# lamloei_unofox_sfm10r4.net
KiCad netlist of a schematic drawn in EAGLE
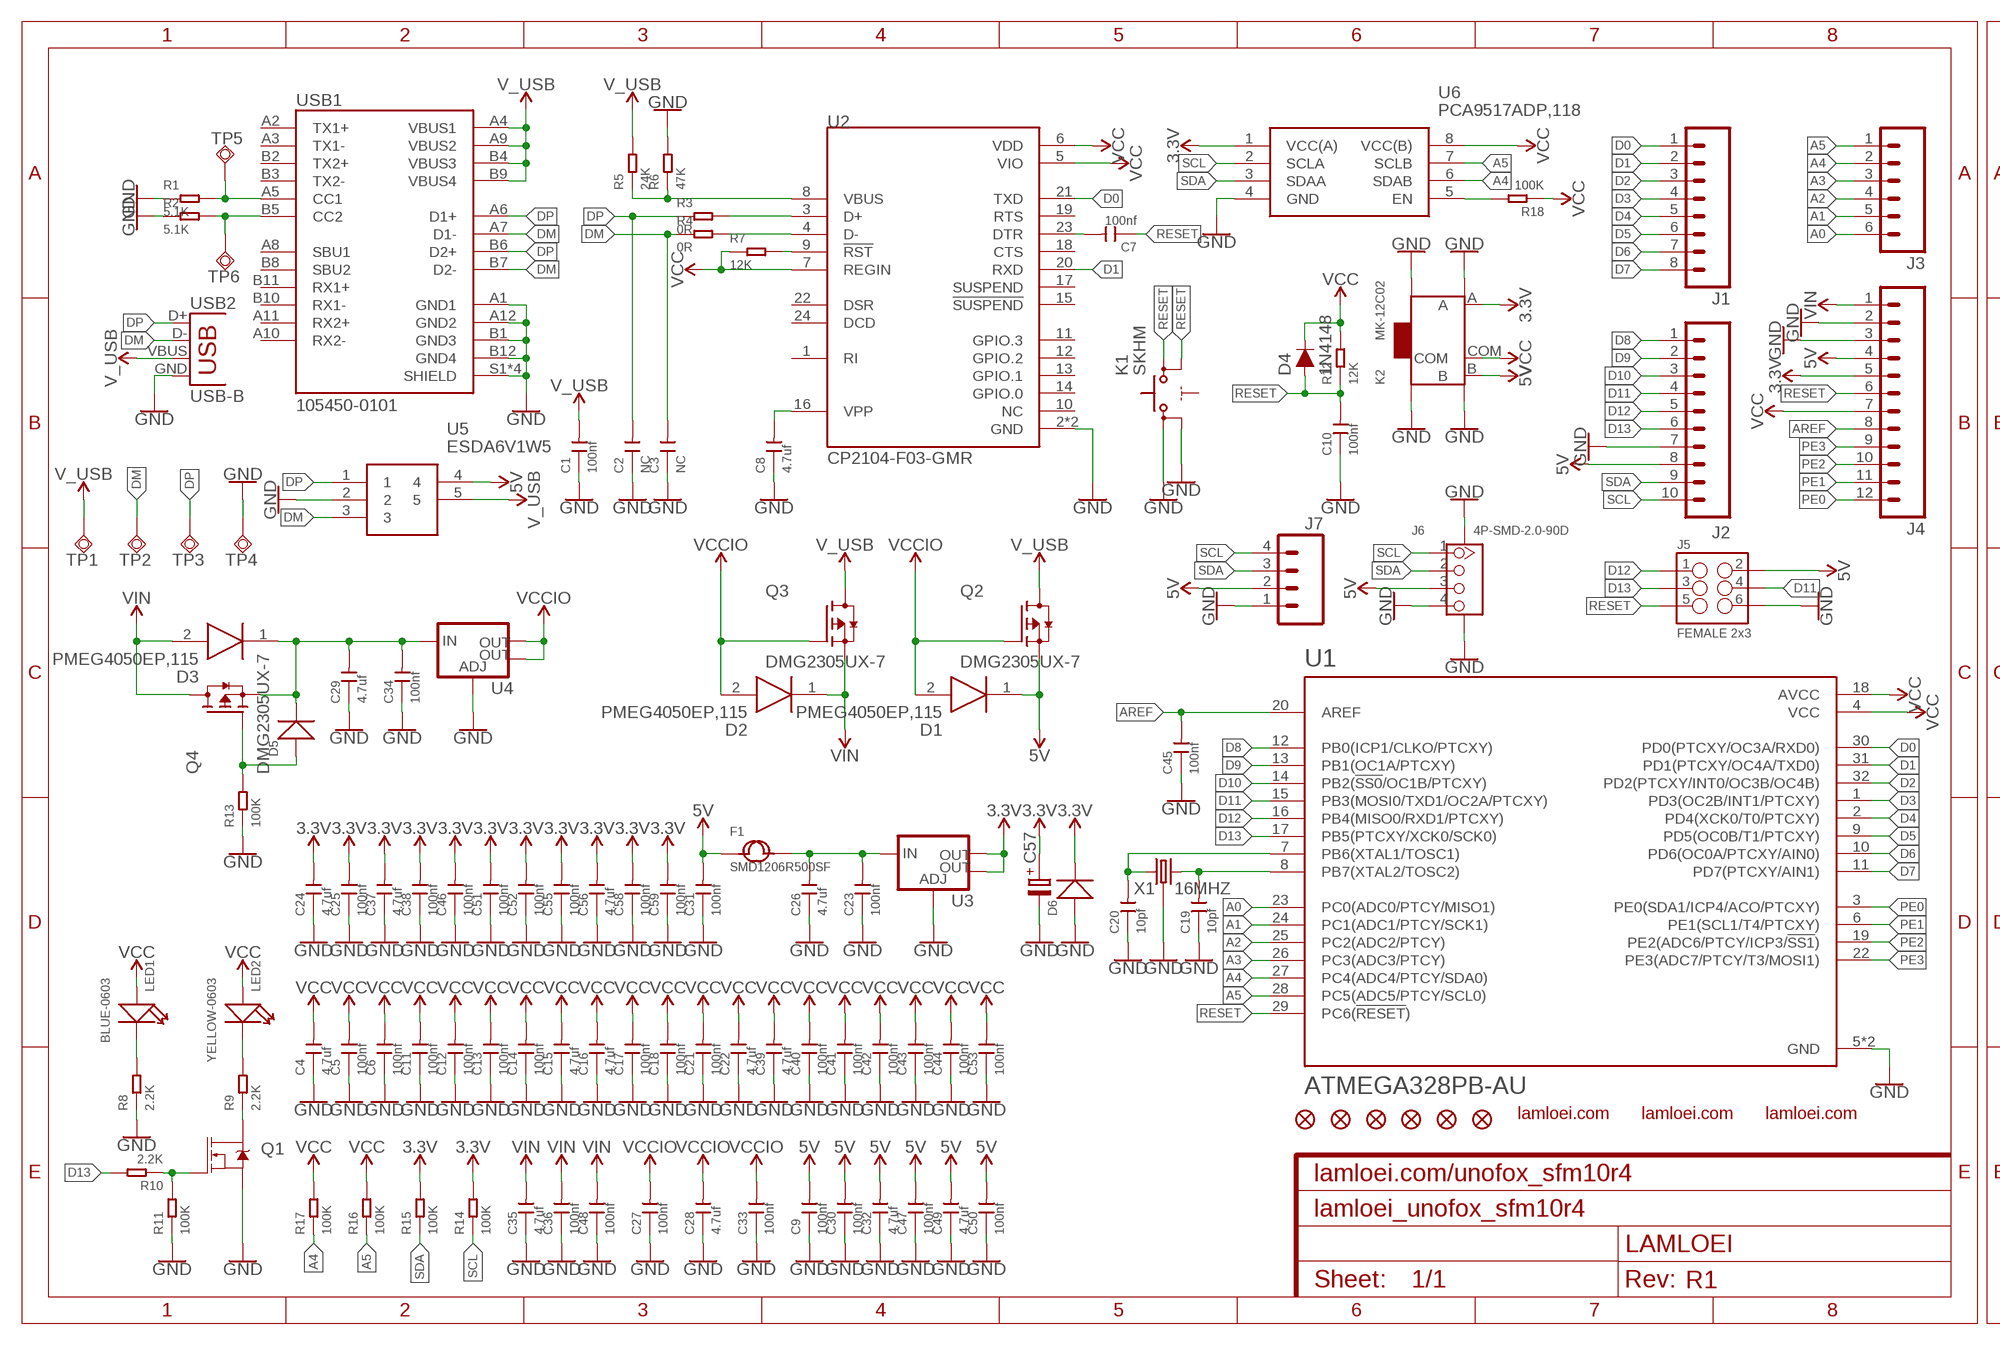
[diagram p0: schematic, sheet 1, part 1 of 2]
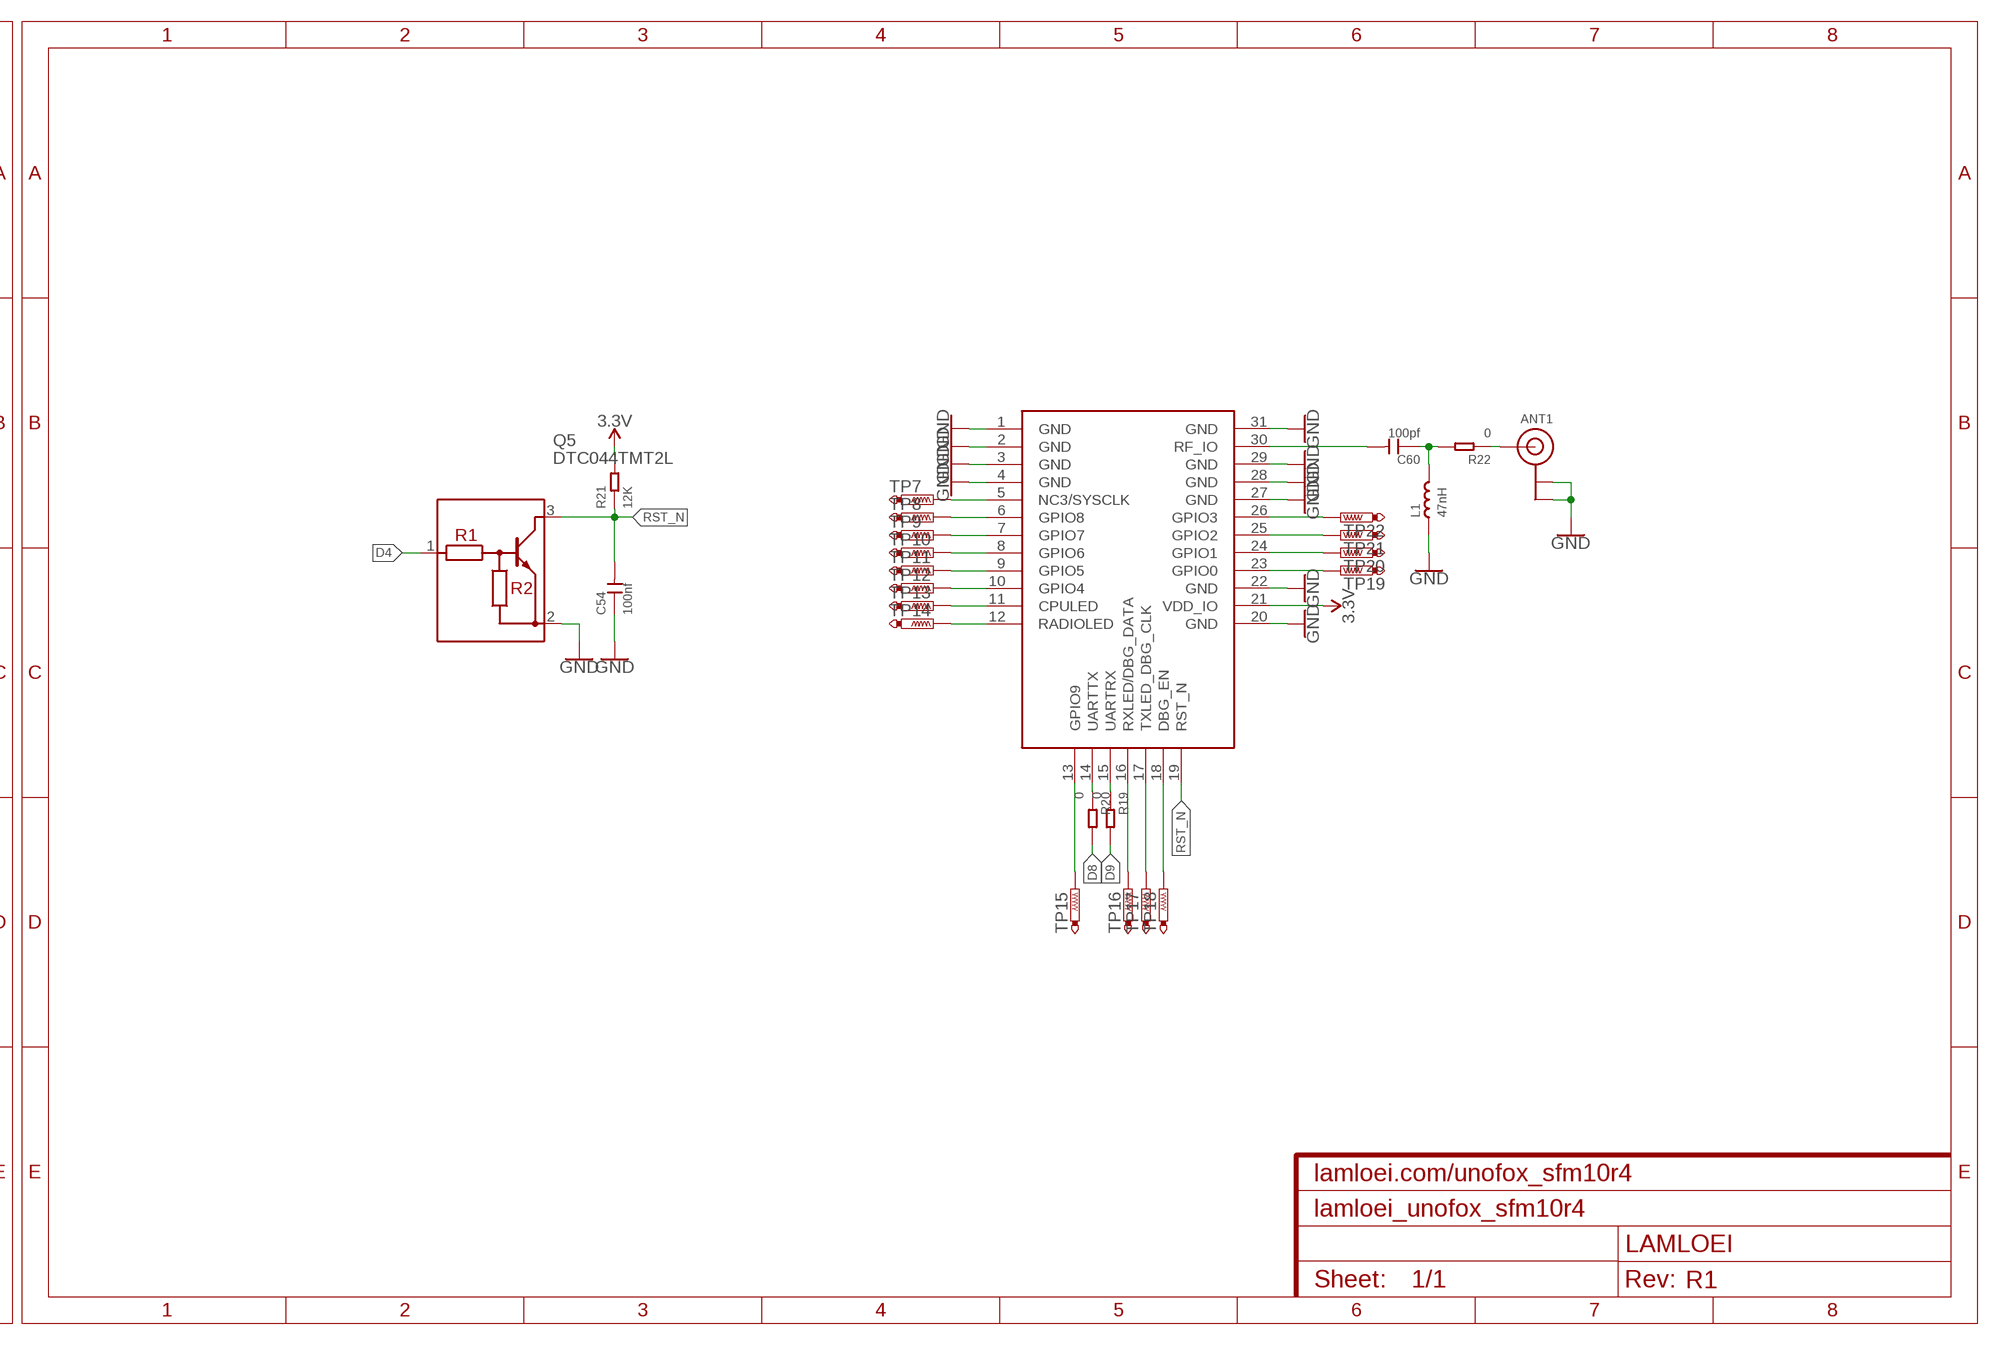
[diagram p1: schematic, sheet 1, part 2 of 2]

(export (version "E")
  (design (tool "Eeschema 10.0.6"))
  (components
    (comp (ref "ANT1")
      (value "ANTENNA_U.FL")
      (footprint "eagle-import:U.FL")
      (libsource (lib "eagle-import") (part "ANTENNA_U.FL"))
    )
    (comp (ref "C1")
      (value "100nf")
      (footprint "eagle-import:C0402")
      (fields (field (name "MPN") "CC0402KRX7R8BB104"))
      (libsource (lib "eagle-import") (part "CERAMIC-100NF-25V-10%-X7R(0402)"))
    )
    (comp (ref "C2")
      (value "NC")
      (footprint "eagle-import:C0402")
      (fields (field (name "MPN") "CC0402JRNPO9BN470"))
      (libsource (lib "eagle-import") (part "CERAMIC-47PF-50V-5%-NP0(0402)"))
    )
    (comp (ref "C3")
      (value "NC")
      (footprint "eagle-import:C0402")
      (fields (field (name "MPN") "CC0402JRNPO9BN470"))
      (libsource (lib "eagle-import") (part "CERAMIC-47PF-50V-5%-NP0(0402)"))
    )
    (comp (ref "C4")
      (value "4.7uf")
      (footprint "eagle-import:C0805")
      (fields (field (name "MPN") "CC0805KKX5R8BB106"))
      (libsource (lib "eagle-import") (part "CERAMIC-10UF-25V-10%-X5R(0805)"))
    )
    (comp (ref "C5")
      (value "100nf")
      (footprint "eagle-import:C0402")
      (fields (field (name "MPN") "CC0402KRX7R8BB104"))
      (libsource (lib "eagle-import") (part "CERAMIC-100NF-25V-10%-X7R(0402)"))
    )
    (comp (ref "C6")
      (value "100nf")
      (footprint "eagle-import:C0402")
      (fields (field (name "MPN") "CC0402KRX7R8BB104"))
      (libsource (lib "eagle-import") (part "CERAMIC-100NF-25V-10%-X7R(0402)"))
    )
    (comp (ref "C7")
      (value "100nf")
      (footprint "eagle-import:C0402")
      (fields (field (name "MPN") "CC0402KRX7R8BB104"))
      (libsource (lib "eagle-import") (part "CERAMIC-100NF-25V-10%-X7R(0402)"))
    )
    (comp (ref "C8")
      (value "4.7uf")
      (footprint "eagle-import:C0805")
      (fields (field (name "MPN") "CC0805KKX5R8BB106"))
      (libsource (lib "eagle-import") (part "CERAMIC-10UF-25V-10%-X5R(0805)"))
    )
    (comp (ref "C9")
      (value "100nf")
      (footprint "eagle-import:C0402")
      (fields (field (name "MPN") "CC0402KRX7R8BB104"))
      (libsource (lib "eagle-import") (part "CERAMIC-100NF-25V-10%-X7R(0402)"))
    )
    (comp (ref "C10")
      (value "100nf")
      (footprint "eagle-import:C0402")
      (fields (field (name "MPN") "CC0402KRX7R8BB104"))
      (libsource (lib "eagle-import") (part "CERAMIC-100NF-25V-10%-X7R(0402)"))
    )
    (comp (ref "C11")
      (value "100nf")
      (footprint "eagle-import:C0402")
      (fields (field (name "MPN") "CC0402KRX7R8BB104"))
      (libsource (lib "eagle-import") (part "CERAMIC-100NF-25V-10%-X7R(0402)"))
    )
    (comp (ref "C12")
      (value "100nf")
      (footprint "eagle-import:C0402")
      (fields (field (name "MPN") "CC0402KRX7R8BB104"))
      (libsource (lib "eagle-import") (part "CERAMIC-100NF-25V-10%-X7R(0402)"))
    )
    (comp (ref "C13")
      (value "100nf")
      (footprint "eagle-import:C0402")
      (fields (field (name "MPN") "CC0402KRX7R8BB104"))
      (libsource (lib "eagle-import") (part "CERAMIC-100NF-25V-10%-X7R(0402)"))
    )
    (comp (ref "C14")
      (value "100nf")
      (footprint "eagle-import:C0402")
      (fields (field (name "MPN") "CC0402KRX7R8BB104"))
      (libsource (lib "eagle-import") (part "CERAMIC-100NF-25V-10%-X7R(0402)"))
    )
    (comp (ref "C15")
      (value "4.7uf")
      (footprint "eagle-import:C0805")
      (fields (field (name "MPN") "CC0805KKX5R8BB106"))
      (libsource (lib "eagle-import") (part "CERAMIC-10UF-25V-10%-X5R(0805)"))
    )
    (comp (ref "C16")
      (value "4.7uf")
      (footprint "eagle-import:C0805")
      (fields (field (name "MPN") "CC0805KKX5R8BB106"))
      (libsource (lib "eagle-import") (part "CERAMIC-10UF-25V-10%-X5R(0805)"))
    )
    (comp (ref "C17")
      (value "100nf")
      (footprint "eagle-import:C0402")
      (fields (field (name "MPN") "CC0402KRX7R8BB104"))
      (libsource (lib "eagle-import") (part "CERAMIC-100NF-25V-10%-X7R(0402)"))
    )
    (comp (ref "C18")
      (value "100nf")
      (footprint "eagle-import:C0402")
      (fields (field (name "MPN") "CC0402KRX7R8BB104"))
      (libsource (lib "eagle-import") (part "CERAMIC-100NF-25V-10%-X7R(0402)"))
    )
    (comp (ref "C19")
      (value "10pf")
      (footprint "eagle-import:C0402")
      (fields (field (name "MPN") "CC0402KRX7R8BB104"))
      (libsource (lib "eagle-import") (part "CERAMIC-100NF-25V-10%-X7R(0402)"))
    )
    (comp (ref "C20")
      (value "10pf")
      (footprint "eagle-import:C0402")
      (fields (field (name "MPN") "CC0402KRX7R8BB104"))
      (libsource (lib "eagle-import") (part "CERAMIC-100NF-25V-10%-X7R(0402)"))
    )
    (comp (ref "C21")
      (value "100nf")
      (footprint "eagle-import:C0402")
      (fields (field (name "MPN") "CC0402KRX7R8BB104"))
      (libsource (lib "eagle-import") (part "CERAMIC-100NF-25V-10%-X7R(0402)"))
    )
    (comp (ref "C22")
      (value "4.7uf")
      (footprint "eagle-import:C0805")
      (fields (field (name "MPN") "CC0805KKX5R8BB106"))
      (libsource (lib "eagle-import") (part "CERAMIC-10UF-25V-10%-X5R(0805)"))
    )
    (comp (ref "C23")
      (value "100nf")
      (footprint "eagle-import:C0402")
      (fields (field (name "MPN") "CC0402KRX7R8BB104"))
      (libsource (lib "eagle-import") (part "CERAMIC-100NF-25V-10%-X7R(0402)"))
    )
    (comp (ref "C24")
      (value "4.7uf")
      (footprint "eagle-import:C0805")
      (fields (field (name "MPN") "CC0805KKX5R8BB106"))
      (libsource (lib "eagle-import") (part "CERAMIC-10UF-25V-10%-X5R(0805)"))
    )
    (comp (ref "C25")
      (value "100nf")
      (footprint "eagle-import:C0402")
      (fields (field (name "MPN") "CC0402KRX7R8BB104"))
      (libsource (lib "eagle-import") (part "CERAMIC-100NF-25V-10%-X7R(0402)"))
    )
    (comp (ref "C26")
      (value "4.7uf")
      (footprint "eagle-import:C0805")
      (fields (field (name "MPN") "CC0805KKX5R8BB106"))
      (libsource (lib "eagle-import") (part "CERAMIC-10UF-25V-10%-X5R(0805)"))
    )
    (comp (ref "C27")
      (value "100nf")
      (footprint "eagle-import:C0402")
      (fields (field (name "MPN") "CC0402KRX7R8BB104"))
      (libsource (lib "eagle-import") (part "CERAMIC-100NF-25V-10%-X7R(0402)"))
    )
    (comp (ref "C28")
      (value "4.7uf")
      (footprint "eagle-import:C0805")
      (fields (field (name "MPN") "CC0805KKX5R8BB106"))
      (libsource (lib "eagle-import") (part "CERAMIC-10UF-25V-10%-X5R(0805)"))
    )
    (comp (ref "C29")
      (value "4.7uf")
      (footprint "eagle-import:C0805")
      (fields (field (name "MPN") "CC0805KKX5R8BB106"))
      (libsource (lib "eagle-import") (part "CERAMIC-10UF-25V-10%-X5R(0805)"))
    )
    (comp (ref "C30")
      (value "100nf")
      (footprint "eagle-import:C0402")
      (fields (field (name "MPN") "CC0402KRX7R8BB104"))
      (libsource (lib "eagle-import") (part "CERAMIC-100NF-25V-10%-X7R(0402)"))
    )
    (comp (ref "C31")
      (value "100nf")
      (footprint "eagle-import:C0402")
      (fields (field (name "MPN") "CC0402KRX7R8BB104"))
      (libsource (lib "eagle-import") (part "CERAMIC-100NF-25V-10%-X7R(0402)"))
    )
    (comp (ref "C32")
      (value "4.7uf")
      (footprint "eagle-import:C0805")
      (fields (field (name "MPN") "CC0805KKX5R8BB106"))
      (libsource (lib "eagle-import") (part "CERAMIC-10UF-25V-10%-X5R(0805)"))
    )
    (comp (ref "C33")
      (value "100nf")
      (footprint "eagle-import:C0402")
      (fields (field (name "MPN") "CC0402KRX7R8BB104"))
      (libsource (lib "eagle-import") (part "CERAMIC-100NF-25V-10%-X7R(0402)"))
    )
    (comp (ref "C34")
      (value "100nf")
      (footprint "eagle-import:C0402")
      (fields (field (name "MPN") "CC0402KRX7R8BB104"))
      (libsource (lib "eagle-import") (part "CERAMIC-100NF-25V-10%-X7R(0402)"))
    )
    (comp (ref "C35")
      (value "4.7uf")
      (footprint "eagle-import:C0805")
      (fields (field (name "MPN") "CC0805KKX5R8BB106"))
      (libsource (lib "eagle-import") (part "CERAMIC-10UF-25V-10%-X5R(0805)"))
    )
    (comp (ref "C36")
      (value "100nf")
      (footprint "eagle-import:C0402")
      (fields (field (name "MPN") "CC0402KRX7R8BB104"))
      (libsource (lib "eagle-import") (part "CERAMIC-100NF-25V-10%-X7R(0402)"))
    )
    (comp (ref "C37")
      (value "4.7uf")
      (footprint "eagle-import:C0805")
      (fields (field (name "MPN") "CC0805KKX5R8BB106"))
      (libsource (lib "eagle-import") (part "CERAMIC-10UF-25V-10%-X5R(0805)"))
    )
    (comp (ref "C38")
      (value "100nf")
      (footprint "eagle-import:C0402")
      (fields (field (name "MPN") "CC0402KRX7R8BB104"))
      (libsource (lib "eagle-import") (part "CERAMIC-100NF-25V-10%-X7R(0402)"))
    )
    (comp (ref "C39")
      (value "4.7uf")
      (footprint "eagle-import:C0805")
      (fields (field (name "MPN") "CC0805KKX5R8BB106"))
      (libsource (lib "eagle-import") (part "CERAMIC-10UF-25V-10%-X5R(0805)"))
    )
    (comp (ref "C40")
      (value "100nf")
      (footprint "eagle-import:C0402")
      (fields (field (name "MPN") "CC0402KRX7R8BB104"))
      (libsource (lib "eagle-import") (part "CERAMIC-100NF-25V-10%-X7R(0402)"))
    )
    (comp (ref "C41")
      (value "100nf")
      (footprint "eagle-import:C0402")
      (fields (field (name "MPN") "CC0402KRX7R8BB104"))
      (libsource (lib "eagle-import") (part "CERAMIC-100NF-25V-10%-X7R(0402)"))
    )
    (comp (ref "C42")
      (value "100nf")
      (footprint "eagle-import:C0402")
      (fields (field (name "MPN") "CC0402KRX7R8BB104"))
      (libsource (lib "eagle-import") (part "CERAMIC-100NF-25V-10%-X7R(0402)"))
    )
    (comp (ref "C43")
      (value "100nf")
      (footprint "eagle-import:C0402")
      (fields (field (name "MPN") "CC0402KRX7R8BB104"))
      (libsource (lib "eagle-import") (part "CERAMIC-100NF-25V-10%-X7R(0402)"))
    )
    (comp (ref "C44")
      (value "100nf")
      (footprint "eagle-import:C0402")
      (fields (field (name "MPN") "CC0402KRX7R8BB104"))
      (libsource (lib "eagle-import") (part "CERAMIC-100NF-25V-10%-X7R(0402)"))
    )
    (comp (ref "C45")
      (value "100nf")
      (footprint "eagle-import:C0402")
      (fields (field (name "MPN") "CC0402KRX7R8BB104"))
      (libsource (lib "eagle-import") (part "CERAMIC-100NF-25V-10%-X7R(0402)"))
    )
    (comp (ref "C46")
      (value "100nf")
      (footprint "eagle-import:C0402")
      (fields (field (name "MPN") "CC0402KRX7R8BB104"))
      (libsource (lib "eagle-import") (part "CERAMIC-100NF-25V-10%-X7R(0402)"))
    )
    (comp (ref "C47")
      (value "100nf")
      (footprint "eagle-import:C0402")
      (fields (field (name "MPN") "CC0402KRX7R8BB104"))
      (libsource (lib "eagle-import") (part "CERAMIC-100NF-25V-10%-X7R(0402)"))
    )
    (comp (ref "C48")
      (value "100nf")
      (footprint "eagle-import:C0402")
      (fields (field (name "MPN") "CC0402KRX7R8BB104"))
      (libsource (lib "eagle-import") (part "CERAMIC-100NF-25V-10%-X7R(0402)"))
    )
    (comp (ref "C49")
      (value "4.7uf")
      (footprint "eagle-import:C0805")
      (fields (field (name "MPN") "CC0805KKX5R8BB106"))
      (libsource (lib "eagle-import") (part "CERAMIC-10UF-25V-10%-X5R(0805)"))
    )
    (comp (ref "C50")
      (value "100nf")
      (footprint "eagle-import:C0402")
      (fields (field (name "MPN") "CC0402KRX7R8BB104"))
      (libsource (lib "eagle-import") (part "CERAMIC-100NF-25V-10%-X7R(0402)"))
    )
    (comp (ref "C51")
      (value "100nf")
      (footprint "eagle-import:C0402")
      (fields (field (name "MPN") "CC0402KRX7R8BB104"))
      (libsource (lib "eagle-import") (part "CERAMIC-100NF-25V-10%-X7R(0402)"))
    )
    (comp (ref "C52")
      (value "100nf")
      (footprint "eagle-import:C0402")
      (fields (field (name "MPN") "CC0402KRX7R8BB104"))
      (libsource (lib "eagle-import") (part "CERAMIC-100NF-25V-10%-X7R(0402)"))
    )
    (comp (ref "C53")
      (value "100nf")
      (footprint "eagle-import:C0402")
      (fields (field (name "MPN") "CC0402KRX7R8BB104"))
      (libsource (lib "eagle-import") (part "CERAMIC-100NF-25V-10%-X7R(0402)"))
    )
    (comp (ref "C54")
      (value "100nf")
      (footprint "eagle-import:C0402")
      (fields (field (name "MPN") "CC0402KRX7R8BB104"))
      (libsource (lib "eagle-import") (part "CERAMIC-100NF-25V-10%-X7R(0402)"))
    )
    (comp (ref "C55")
      (value "100nf")
      (footprint "eagle-import:C0402")
      (fields (field (name "MPN") "CC0402KRX7R8BB104"))
      (libsource (lib "eagle-import") (part "CERAMIC-100NF-25V-10%-X7R(0402)"))
    )
    (comp (ref "C56")
      (value "4.7uf")
      (footprint "eagle-import:C0805")
      (fields (field (name "MPN") "CC0805KKX5R8BB106"))
      (libsource (lib "eagle-import") (part "CERAMIC-10UF-25V-10%-X5R(0805)"))
    )
    (comp (ref "C57")
      (value "C-PR-SMD-TE-D")
      (footprint "eagle-import:TE-D-7343")
      (libsource (lib "eagle-import") (part "C-PR-SMD-TE-D"))
    )
    (comp (ref "C58")
      (value "100nf")
      (footprint "eagle-import:C0402")
      (fields (field (name "MPN") "CC0402KRX7R8BB104"))
      (libsource (lib "eagle-import") (part "CERAMIC-100NF-25V-10%-X7R(0402)"))
    )
    (comp (ref "C59")
      (value "100nf")
      (footprint "eagle-import:C0402")
      (fields (field (name "MPN") "CC0402KRX7R8BB104"))
      (libsource (lib "eagle-import") (part "CERAMIC-100NF-25V-10%-X7R(0402)"))
    )
    (comp (ref "C60")
      (value "100pf")
      (footprint "eagle-import:C0402")
      (fields (field (name "MPN") "CC0402KRX7R8BB104"))
      (libsource (lib "eagle-import") (part "CERAMIC-100NF-25V-10%-X7R(0402)"))
    )
    (comp (ref "D1")
      (value "PMEG4050EP,115")
      (footprint "eagle-import:SODFL4725X110N")
      (fields (field (name "RS_PART_NUMBER") "7805405P"))
      (libsource (lib "eagle-import") (part "PMEG4050EP,115"))
    )
    (comp (ref "D2")
      (value "PMEG4050EP,115")
      (footprint "eagle-import:SODFL4725X110N")
      (fields (field (name "RS_PART_NUMBER") "7805405P"))
      (libsource (lib "eagle-import") (part "PMEG4050EP,115"))
    )
    (comp (ref "D3")
      (value "PMEG4050EP,115")
      (footprint "eagle-import:SODFL4725X110N")
      (fields (field (name "RS_PART_NUMBER") "7805405P"))
      (libsource (lib "eagle-import") (part "PMEG4050EP,115"))
    )
    (comp (ref "D4")
      (value "1N4148")
      (footprint "eagle-import:SOD-323")
      (libsource (lib "eagle-import") (part "DIODE-BAS16J"))
    )
    (comp (ref "D5")
      (value "DIODE'1N4148-SMD'")
      (footprint "eagle-import:LL-34")
      (libsource (lib "eagle-import") (part "DIODE'1N4148-SMD'"))
    )
    (comp (ref "D6")
      (value "DIODE'1N4148-SMD'")
      (footprint "eagle-import:LL-34")
      (libsource (lib "eagle-import") (part "DIODE'1N4148-SMD'"))
    )
    (comp (ref "F1")
      (value "SMD1206R500SF")
      (footprint "eagle-import:F1206")
      (libsource (lib "eagle-import") (part "SMD-PPTC-500MA(1206)"))
    )
    (comp (ref "J1")
      (value "M08SILK_FEMALE_PTH")
      (footprint "eagle-import:1X08")
      (libsource (lib "eagle-import") (part "M08SILK_FEMALE_PTH"))
    )
    (comp (ref "J2")
      (value "M10SILK_FEMALE_PTH")
      (footprint "eagle-import:1X10")
      (libsource (lib "eagle-import") (part "M10SILK_FEMALE_PTH"))
    )
    (comp (ref "J3")
      (value "M06SILK_FEMALE_PTH")
      (footprint "eagle-import:1X06")
      (libsource (lib "eagle-import") (part "M06SILK_FEMALE_PTH"))
    )
    (comp (ref "J4")
      (value "M12PTH")
      (footprint "eagle-import:1X12")
      (libsource (lib "eagle-import") (part "M12PTH"))
    )
    (comp (ref "J5")
      (value "FEMALE 2x3")
      (footprint "eagle-import:2X3")
      (libsource (lib "eagle-import") (part "M03X2FEMALE"))
    )
    (comp (ref "J6")
      (value "4P-SMD-2.0-90D")
      (footprint "eagle-import:HW4-SMD-2.0-90D")
      (libsource (lib "eagle-import") (part "GROVE-CONNECTOR-SMD-90D(4+2P-2.0)"))
    )
    (comp (ref "J7")
      (value "M04LONGPADS")
      (footprint "eagle-import:1X04_LONGPADS")
      (libsource (lib "eagle-import") (part "M04LONGPADS"))
    )
    (comp (ref "K1")
      (value "SKHM")
      (footprint "eagle-import:SKHM")
      (libsource (lib "eagle-import") (part "SKHM"))
    )
    (comp (ref "K2")
      (value "MK-12C02")
      (footprint "eagle-import:SW7-SMD-L6.7X2.7X3.2MM")
      (libsource (lib "eagle-import") (part "SMD-TOGGLE-SWITCH-ON-ON(3+4P-6.7X2.7MM)"))
    )
    (comp (ref "L1")
      (value "47nH")
      (footprint "eagle-import:L0603")
      (libsource (lib "eagle-import") (part "SMD-INDUCTOR-68NH-10%(0603)"))
    )
    (comp (ref "LED1")
      (value "BLUE-0603")
      (footprint "eagle-import:LED-0603")
      (fields (field (name "MPN") "19-217-BHC-ZL1M2RY-3T"))
      (libsource (lib "eagle-import") (part "SMD-LED-CLEAR-BLUE(0603)"))
    )
    (comp (ref "LED2")
      (value "YELLOW-0603")
      (footprint "eagle-import:LED-0603")
      (fields (field (name "MPN") "19-217-BHC-ZL1M2RY-3T"))
      (libsource (lib "eagle-import") (part "SMD-LED-CLEAR-BLUE(0603)"))
    )
    (comp (ref "Q1")
      (value "220mA/50V/3.5Ω")
      (footprint "eagle-import:SOT23-3")
      (libsource (lib "eagle-import") (part "MOSFET-NCH-BSS138"))
    )
    (comp (ref "Q2")
      (value "DMG2305UX-7")
      (footprint "eagle-import:SOT91P240X110-3N_DMG2305UX-7")
      (fields (field (name "MF") "Diodes Inc."))
      (libsource (lib "eagle-import") (part "DMG2305UX-7"))
    )
    (comp (ref "Q3")
      (value "DMG2305UX-7")
      (footprint "eagle-import:SOT91P240X110-3N_DMG2305UX-7")
      (fields (field (name "MF") "Diodes Inc."))
      (libsource (lib "eagle-import") (part "DMG2305UX-7"))
    )
    (comp (ref "Q4")
      (value "DMG2305UX-7")
      (footprint "eagle-import:SOT91P240X110-3N_DMG2305UX-7")
      (fields (field (name "MF") "Diodes Inc."))
      (libsource (lib "eagle-import") (part "DMG2305UX-7"))
    )
    (comp (ref "Q5")
      (value "DTC044TMT2L")
      (footprint "eagle-import:SOTFL40P120X55-3N")
      (fields (field (name "RS_PART_NUMBER") "1467267"))
      (libsource (lib "eagle-import") (part "DTC044TMT2L"))
    )
    (comp (ref "R1")
      (value "5.1K")
      (footprint "eagle-import:R0402")
      (fields (field (name "MPN") "RC0402JR-074K7L"))
      (libsource (lib "eagle-import") (part "SMD-RES-4.7K-5%-1/16W(0402)"))
    )
    (comp (ref "R2")
      (value "5.1K")
      (footprint "eagle-import:R0402")
      (fields (field (name "MPN") "RC0402JR-074K7L"))
      (libsource (lib "eagle-import") (part "SMD-RES-4.7K-5%-1/16W(0402)"))
    )
    (comp (ref "R3")
      (value "0R")
      (footprint "eagle-import:R0402")
      (fields (field (name "MPN") "RC0402FR-0722RL"))
      (libsource (lib "eagle-import") (part "SMD-RES-22R-1%-1/16W(0402)"))
    )
    (comp (ref "R4")
      (value "0R")
      (footprint "eagle-import:R0402")
      (fields (field (name "MPN") "RC0402FR-0722RL"))
      (libsource (lib "eagle-import") (part "SMD-RES-22R-1%-1/16W(0402)"))
    )
    (comp (ref "R5")
      (value "24K")
      (footprint "eagle-import:R0402")
      (fields (field (name "MPN") "RC0402FR-0722RL"))
      (libsource (lib "eagle-import") (part "SMD-RES-22R-1%-1/16W(0402)"))
    )
    (comp (ref "R6")
      (value "47K")
      (footprint "eagle-import:R0402")
      (fields (field (name "MPN") "RC0402FR-0722RL"))
      (libsource (lib "eagle-import") (part "SMD-RES-22R-1%-1/16W(0402)"))
    )
    (comp (ref "R7")
      (value "12K")
      (footprint "eagle-import:R0402")
      (fields (field (name "MPN") "RC0402FR-0710KL"))
      (libsource (lib "eagle-import") (part "SMD-RES-10K-1%-1/16W(0402)"))
    )
    (comp (ref "R8")
      (value "2.2K")
      (footprint "eagle-import:R0402")
      (fields (field (name "MPN") "RC0402FR-072K7L"))
      (libsource (lib "eagle-import") (part "SMD-RES-2.7K-1%-1/16W(0402)"))
    )
    (comp (ref "R9")
      (value "2.2K")
      (footprint "eagle-import:R0402")
      (fields (field (name "MPN") "RC0402FR-072K7L"))
      (libsource (lib "eagle-import") (part "SMD-RES-2.7K-1%-1/16W(0402)"))
    )
    (comp (ref "R10")
      (value "2.2K")
      (footprint "eagle-import:R0402")
      (fields (field (name "MPN") "RC0402FR-072K7L"))
      (libsource (lib "eagle-import") (part "SMD-RES-2.7K-1%-1/16W(0402)"))
    )
    (comp (ref "R11")
      (value "100K")
      (footprint "eagle-import:R0402")
      (fields (field (name "MPN") "RC0402FR-0710KL"))
      (libsource (lib "eagle-import") (part "SMD-RES-10K-1%-1/16W(0402)"))
    )
    (comp (ref "R12")
      (value "12K")
      (footprint "eagle-import:R0402")
      (fields (field (name "MPN") "RC0402FR-0710KL"))
      (libsource (lib "eagle-import") (part "SMD-RES-10K-1%-1/16W(0402)"))
    )
    (comp (ref "R13")
      (value "100K")
      (footprint "eagle-import:R0402")
      (fields (field (name "MPN") "RC0402FR-0710KL"))
      (libsource (lib "eagle-import") (part "SMD-RES-10K-1%-1/16W(0402)"))
    )
    (comp (ref "R14")
      (value "100K")
      (footprint "eagle-import:R0402")
      (fields (field (name "MPN") "RC0402FR-0710KL"))
      (libsource (lib "eagle-import") (part "SMD-RES-10K-1%-1/16W(0402)"))
    )
    (comp (ref "R15")
      (value "100K")
      (footprint "eagle-import:R0402")
      (fields (field (name "MPN") "RC0402FR-0710KL"))
      (libsource (lib "eagle-import") (part "SMD-RES-10K-1%-1/16W(0402)"))
    )
    (comp (ref "R16")
      (value "100K")
      (footprint "eagle-import:R0402")
      (fields (field (name "MPN") "RC0402FR-0710KL"))
      (libsource (lib "eagle-import") (part "SMD-RES-10K-1%-1/16W(0402)"))
    )
    (comp (ref "R17")
      (value "100K")
      (footprint "eagle-import:R0402")
      (fields (field (name "MPN") "RC0402FR-0710KL"))
      (libsource (lib "eagle-import") (part "SMD-RES-10K-1%-1/16W(0402)"))
    )
    (comp (ref "R18")
      (value "100K")
      (footprint "eagle-import:R0402")
      (fields (field (name "MPN") "RC0402FR-0710KL"))
      (libsource (lib "eagle-import") (part "SMD-RES-10K-1%-1/16W(0402)"))
    )
    (comp (ref "R19")
      (value "0")
      (footprint "eagle-import:R0402")
      (fields (field (name "MPN") "RC0402FR-0710KL"))
      (libsource (lib "eagle-import") (part "SMD-RES-10K-1%-1/16W(0402)"))
    )
    (comp (ref "R20")
      (value "0")
      (footprint "eagle-import:R0402")
      (fields (field (name "MPN") "RC0402FR-0710KL"))
      (libsource (lib "eagle-import") (part "SMD-RES-10K-1%-1/16W(0402)"))
    )
    (comp (ref "R21")
      (value "12K")
      (footprint "eagle-import:R0402")
      (fields (field (name "MPN") "RC0402FR-0710KL"))
      (libsource (lib "eagle-import") (part "SMD-RES-10K-1%-1/16W(0402)"))
    )
    (comp (ref "R22")
      (value "0")
      (footprint "eagle-import:R0402")
      (fields (field (name "MPN") "RC0402FR-0710KL"))
      (libsource (lib "eagle-import") (part "SMD-RES-10K-1%-1/16W(0402)"))
    )
    (comp (ref "TP1")
      (value "TPSQTP13SQ")
      (footprint "eagle-import:TP13SQ")
      (libsource (lib "eagle-import") (part "TPSQTP13SQ"))
    )
    (comp (ref "TP2")
      (value "TPSQTP13SQ")
      (footprint "eagle-import:TP13SQ")
      (libsource (lib "eagle-import") (part "TPSQTP13SQ"))
    )
    (comp (ref "TP3")
      (value "TPSQTP13SQ")
      (footprint "eagle-import:TP13SQ")
      (libsource (lib "eagle-import") (part "TPSQTP13SQ"))
    )
    (comp (ref "TP4")
      (value "TPSQTP13SQ")
      (footprint "eagle-import:TP13SQ")
      (libsource (lib "eagle-import") (part "TPSQTP13SQ"))
    )
    (comp (ref "TP5")
      (value "TPSQTP13SQ")
      (footprint "eagle-import:TP13SQ")
      (libsource (lib "eagle-import") (part "TPSQTP13SQ"))
    )
    (comp (ref "TP6")
      (value "TPSQTP13SQ")
      (footprint "eagle-import:TP13SQ")
      (libsource (lib "eagle-import") (part "TPSQTP13SQ"))
    )
    (comp (ref "TP7")
      (value "PTR1B1,27")
      (footprint "eagle-import:B1,27")
      (libsource (lib "eagle-import") (part "PTR1B1,27"))
    )
    (comp (ref "TP8")
      (value "PTR1B1,27")
      (footprint "eagle-import:B1,27")
      (libsource (lib "eagle-import") (part "PTR1B1,27"))
    )
    (comp (ref "TP9")
      (value "PTR1B1,27")
      (footprint "eagle-import:B1,27")
      (libsource (lib "eagle-import") (part "PTR1B1,27"))
    )
    (comp (ref "TP10")
      (value "PTR1B1,27")
      (footprint "eagle-import:B1,27")
      (libsource (lib "eagle-import") (part "PTR1B1,27"))
    )
    (comp (ref "TP11")
      (value "PTR1B1,27")
      (footprint "eagle-import:B1,27")
      (libsource (lib "eagle-import") (part "PTR1B1,27"))
    )
    (comp (ref "TP12")
      (value "PTR1B1,27")
      (footprint "eagle-import:B1,27")
      (libsource (lib "eagle-import") (part "PTR1B1,27"))
    )
    (comp (ref "TP13")
      (value "PTR1B1,27")
      (footprint "eagle-import:B1,27")
      (libsource (lib "eagle-import") (part "PTR1B1,27"))
    )
    (comp (ref "TP14")
      (value "PTR1B1,27")
      (footprint "eagle-import:B1,27")
      (libsource (lib "eagle-import") (part "PTR1B1,27"))
    )
    (comp (ref "TP15")
      (value "PTR1B1,27")
      (footprint "eagle-import:B1,27")
      (libsource (lib "eagle-import") (part "PTR1B1,27"))
    )
    (comp (ref "TP16")
      (value "PTR1B1,27")
      (footprint "eagle-import:B1,27")
      (libsource (lib "eagle-import") (part "PTR1B1,27"))
    )
    (comp (ref "TP17")
      (value "PTR1B1,27")
      (footprint "eagle-import:B1,27")
      (libsource (lib "eagle-import") (part "PTR1B1,27"))
    )
    (comp (ref "TP18")
      (value "PTR1B1,27")
      (footprint "eagle-import:B1,27")
      (libsource (lib "eagle-import") (part "PTR1B1,27"))
    )
    (comp (ref "TP19")
      (value "PTR1B1,27")
      (footprint "eagle-import:B1,27")
      (libsource (lib "eagle-import") (part "PTR1B1,27"))
    )
    (comp (ref "TP20")
      (value "PTR1B1,27")
      (footprint "eagle-import:B1,27")
      (libsource (lib "eagle-import") (part "PTR1B1,27"))
    )
    (comp (ref "TP21")
      (value "PTR1B1,27")
      (footprint "eagle-import:B1,27")
      (libsource (lib "eagle-import") (part "PTR1B1,27"))
    )
    (comp (ref "TP22")
      (value "PTR1B1,27")
      (footprint "eagle-import:B1,27")
      (libsource (lib "eagle-import") (part "PTR1B1,27"))
    )
    (comp (ref "U1")
      (value "ATMEGA328PB-AU")
      (footprint "eagle-import:QFP80P900X900X120-32N")
      (fields (field (name "MF") "Microchip Technology"))
      (libsource (lib "eagle-import") (part "ATMEGA328PB-AU"))
    )
    (comp (ref "U2")
      (value "CP2104-F03-GMR")
      (footprint "eagle-import:CP2104-F03-GMR")
      (fields (field (name "LCSC_PART") "C47742") (field (name "MF") "Silicon Labs"))
      (libsource (lib "eagle-import") (part "CP2104-F03-GMR"))
    )
    (comp (ref "U3")
      (value "V_REG_LM1117SOT223")
      (footprint "eagle-import:SOT223")
      (libsource (lib "eagle-import") (part "V_REG_LM1117SOT223"))
    )
    (comp (ref "U4")
      (value "V_REG_LM1117SOT223")
      (footprint "eagle-import:SOT223")
      (libsource (lib "eagle-import") (part "V_REG_LM1117SOT223"))
    )
    (comp (ref "U5")
      (value "ESDA6V1W5")
      (footprint "eagle-import:SOT65P210X110-5N")
      (fields (field (name "RS_PART_NUMBER") "1685770"))
      (libsource (lib "eagle-import") (part "ESDA6V1W5"))
    )
    (comp (ref "U6")
      (value "PCA9517ADP,118")
      (footprint "eagle-import:SOP65P490X110-8N")
      (fields (field (name "RS_PART_NUMBER") "7258745P"))
      (libsource (lib "eagle-import") (part "PCA9517ADP,118"))
    )
    (comp (ref "U7")
      (value "WSSFM10RWSSFM10R2R4")
      (footprint "eagle-import:WSSFM10R")
      (libsource (lib "eagle-import") (part "WSSFM10RWSSFM10R2R4"))
    )
    (comp (ref "USB1")
      (value "105450-0101")
      (footprint "eagle-import:105450-0101")
      (fields (field (name "MF") "Molex"))
      (libsource (lib "eagle-import") (part "105450-0101"))
    )
    (comp (ref "USB2")
      (value "USB-B")
      (footprint "eagle-import:USB-B-PTH")
      (libsource (lib "eagle-import") (part "USBPTH"))
    )
    (comp (ref "X1")
      (value "16MHZ")
      (footprint "eagle-import:CRYSTAL-SMD-3.2X2.5MM")
      (libsource (lib "eagle-import") (part "CRYSTAL-26MHZSMD-3.2X2.5"))
    )
    (comp (ref "ZFC1")
      (value "FIDUCIAL1X2")
      (footprint "eagle-import:FIDUCIAL-1X2")
      (libsource (lib "eagle-import") (part "FIDUCIAL1X2"))
    )
    (comp (ref "ZFC2")
      (value "FIDUCIAL1X2")
      (footprint "eagle-import:FIDUCIAL-1X2")
      (libsource (lib "eagle-import") (part "FIDUCIAL1X2"))
    )
    (comp (ref "ZFC3")
      (value "FIDUCIAL1X2")
      (footprint "eagle-import:FIDUCIAL-1X2")
      (libsource (lib "eagle-import") (part "FIDUCIAL1X2"))
    )
    (comp (ref "ZFD1")
      (value "FIDUCIAL1X2")
      (footprint "eagle-import:FIDUCIAL-1X2")
      (libsource (lib "eagle-import") (part "FIDUCIAL1X2"))
    )
    (comp (ref "ZFD2")
      (value "FIDUCIAL1X2")
      (footprint "eagle-import:FIDUCIAL-1X2")
      (libsource (lib "eagle-import") (part "FIDUCIAL1X2"))
    )
    (comp (ref "ZFD3")
      (value "FIDUCIAL1X2")
      (footprint "eagle-import:FIDUCIAL-1X2")
      (libsource (lib "eagle-import") (part "FIDUCIAL1X2"))
    )
    (comp (ref "ZL1")
      (value "LAMLEOI_LOGO_3")
      (footprint "eagle-import:LAMLEOI_LOGO_3")
      (libsource (lib "eagle-import") (part "LAMLEOI_LOGO_3"))
    )
    (comp (ref "ZL2")
      (value "LAMLEOI_LOGO_3")
      (footprint "eagle-import:LAMLEOI_LOGO_3")
      (libsource (lib "eagle-import") (part "LAMLEOI_LOGO_3"))
    )
    (comp (ref "ZL3")
      (value "LAMLOEI_BIGLOGO")
      (footprint "eagle-import:LAMLOEI_BIGLOGO")
      (libsource (lib "eagle-import") (part "LAMLOEI_BIGLOGO"))
    )
  )
  (nets
    (net (code "1") (name "3.3V") (class "Default")
      (node (ref "C24") (pin "2") (pinfunction "2_2") (pintype "passive"))
      (node (ref "C25") (pin "2") (pinfunction "2_2") (pintype "passive"))
      (node (ref "C37") (pin "2") (pinfunction "2_2") (pintype "passive"))
      (node (ref "C38") (pin "2") (pinfunction "2_2") (pintype "passive"))
      (node (ref "C46") (pin "2") (pinfunction "2_2") (pintype "passive"))
      (node (ref "C51") (pin "2") (pinfunction "2_2") (pintype "passive"))
      (node (ref "C52") (pin "2") (pinfunction "2_2") (pintype "passive"))
      (node (ref "C55") (pin "2") (pinfunction "2_2") (pintype "passive"))
      (node (ref "C56") (pin "2") (pinfunction "2_2") (pintype "passive"))
      (node (ref "C57") (pin "+") (pinfunction "+_+") (pintype "passive"))
      (node (ref "C58") (pin "2") (pinfunction "2_2") (pintype "passive"))
      (node (ref "C59") (pin "2") (pinfunction "2_2") (pintype "passive"))
      (node (ref "D6") (pin "C") (pinfunction "-_C") (pintype "passive"))
      (node (ref "J4") (pin "5") (pinfunction "5_5") (pintype "passive"))
      (node (ref "K2") (pin "A") (pinfunction "A_A") (pintype "bidirectional"))
      (node (ref "R14") (pin "2") (pinfunction "2_2") (pintype "passive"))
      (node (ref "R15") (pin "2") (pinfunction "2_2") (pintype "passive"))
      (node (ref "R21") (pin "2") (pinfunction "2_2") (pintype "passive"))
      (node (ref "U3") (pin "2") (pinfunction "OUT_2") (pintype "output"))
      (node (ref "U3") (pin "4") (pinfunction "OUT_4") (pintype "output"))
      (node (ref "U6") (pin "1") (pinfunction "VCC(A)_1") (pintype "bidirectional"))
      (node (ref "U7") (pin "21") (pinfunction "VDD_IO_21") (pintype "bidirectional"))
    )
    (net (code "2") (name "5V") (class "Default")
      (node (ref "C30") (pin "2") (pinfunction "2_2") (pintype "passive"))
      (node (ref "C31") (pin "2") (pinfunction "2_2") (pintype "passive"))
      (node (ref "C32") (pin "2") (pinfunction "2_2") (pintype "passive"))
      (node (ref "C47") (pin "2") (pinfunction "2_2") (pintype "passive"))
      (node (ref "C49") (pin "2") (pinfunction "2_2") (pintype "passive"))
      (node (ref "C50") (pin "2") (pinfunction "2_2") (pintype "passive"))
      (node (ref "C9") (pin "2") (pinfunction "2_2") (pintype "passive"))
      (node (ref "D1") (pin "1") (pinfunction "K_1") (pintype "bidirectional"))
      (node (ref "F1") (pin "1") (pinfunction "1_1") (pintype "bidirectional"))
      (node (ref "J2") (pin "8") (pinfunction "8_8") (pintype "passive"))
      (node (ref "J4") (pin "4") (pinfunction "4_4") (pintype "passive"))
      (node (ref "J5") (pin "2") (pinfunction "2_2") (pintype "bidirectional"))
      (node (ref "J6") (pin "3") (pinfunction "3_3") (pintype "bidirectional"))
      (node (ref "J7") (pin "2") (pinfunction "2_2") (pintype "passive"))
      (node (ref "K2") (pin "B") (pinfunction "B_B") (pintype "bidirectional"))
      (node (ref "Q2") (pin "2") (pinfunction "S_2") (pintype "passive"))
      (node (ref "U5") (pin "4") (pinfunction "4_4") (pintype "bidirectional"))
    )
    (net (code "3") (name "A0") (class "Default")
      (node (ref "J3") (pin "6") (pinfunction "6_6") (pintype "passive"))
      (node (ref "U1") (pin "23") (pinfunction "PC0(ADC0/PTCY/MISO1)_23") (pintype "bidirectional"))
    )
    (net (code "4") (name "A1") (class "Default")
      (node (ref "J3") (pin "5") (pinfunction "5_5") (pintype "passive"))
      (node (ref "U1") (pin "24") (pinfunction "PC1(ADC1/PTCY/SCK1)_24") (pintype "bidirectional"))
    )
    (net (code "5") (name "A2") (class "Default")
      (node (ref "J3") (pin "4") (pinfunction "4_4") (pintype "passive"))
      (node (ref "U1") (pin "25") (pinfunction "PC2(ADC2/PTCY)_25") (pintype "bidirectional"))
    )
    (net (code "6") (name "A3") (class "Default")
      (node (ref "J3") (pin "3") (pinfunction "3_3") (pintype "passive"))
      (node (ref "U1") (pin "26") (pinfunction "PC3(ADC3/PTCY)_26") (pintype "bidirectional"))
    )
    (net (code "7") (name "A4") (class "Default")
      (node (ref "J3") (pin "2") (pinfunction "2_2") (pintype "passive"))
      (node (ref "R17") (pin "1") (pinfunction "1_1") (pintype "passive"))
      (node (ref "U1") (pin "27") (pinfunction "PC4(ADC4/PTCY/SDA0)_27") (pintype "bidirectional"))
      (node (ref "U6") (pin "6") (pinfunction "SDAB_6") (pintype "bidirectional"))
    )
    (net (code "8") (name "A5") (class "Default")
      (node (ref "J3") (pin "1") (pinfunction "1_1") (pintype "passive"))
      (node (ref "R16") (pin "1") (pinfunction "1_1") (pintype "passive"))
      (node (ref "U1") (pin "28") (pinfunction "PC5(ADC5/PTCY/SCL0)_28") (pintype "bidirectional"))
      (node (ref "U6") (pin "7") (pinfunction "SCLB_7") (pintype "bidirectional"))
    )
    (net (code "9") (name "AREF") (class "Default")
      (node (ref "C45") (pin "2") (pinfunction "2_2") (pintype "passive"))
      (node (ref "J4") (pin "8") (pinfunction "8_8") (pintype "passive"))
      (node (ref "U1") (pin "20") (pinfunction "AREF_20") (pintype "input"))
    )
    (net (code "10") (name "D0") (class "Default")
      (node (ref "J1") (pin "1") (pinfunction "1_1") (pintype "passive"))
      (node (ref "U1") (pin "30") (pinfunction "PD0(PTCXY/OC3A/RXD0)_30") (pintype "bidirectional"))
      (node (ref "U2") (pin "21") (pinfunction "TXD_21") (pintype "output"))
    )
    (net (code "11") (name "D1") (class "Default")
      (node (ref "J1") (pin "2") (pinfunction "2_2") (pintype "passive"))
      (node (ref "U1") (pin "31") (pinfunction "PD1(PTCXY/OC4A/TXD0)_31") (pintype "bidirectional"))
      (node (ref "U2") (pin "20") (pinfunction "RXD_20") (pintype "input"))
    )
    (net (code "12") (name "D2") (class "Default")
      (node (ref "J1") (pin "3") (pinfunction "3_3") (pintype "passive"))
      (node (ref "U1") (pin "32") (pinfunction "PD2(PTCXY/INT0/OC3B/OC4B)_32") (pintype "bidirectional"))
    )
    (net (code "13") (name "D3") (class "Default")
      (node (ref "J1") (pin "4") (pinfunction "4_4") (pintype "passive"))
      (node (ref "U1") (pin "1") (pinfunction "PD3(OC2B/INT1/PTCXY)_1") (pintype "bidirectional"))
    )
    (net (code "14") (name "D4") (class "Default")
      (node (ref "J1") (pin "5") (pinfunction "5_5") (pintype "passive"))
      (node (ref "Q5") (pin "1") (pinfunction "B_1") (pintype "bidirectional"))
      (node (ref "U1") (pin "2") (pinfunction "PD4(XCK0/T0/PTCXY)_2") (pintype "bidirectional"))
    )
    (net (code "15") (name "D5") (class "Default")
      (node (ref "J1") (pin "6") (pinfunction "6_6") (pintype "passive"))
      (node (ref "U1") (pin "9") (pinfunction "PD5(OC0B/T1/PTCXY)_9") (pintype "bidirectional"))
    )
    (net (code "16") (name "D6") (class "Default")
      (node (ref "J1") (pin "7") (pinfunction "7_7") (pintype "passive"))
      (node (ref "U1") (pin "10") (pinfunction "PD6(OC0A/PTCXY/AIN0)_10") (pintype "bidirectional"))
    )
    (net (code "17") (name "D7") (class "Default")
      (node (ref "J1") (pin "8") (pinfunction "8_8") (pintype "passive"))
      (node (ref "U1") (pin "11") (pinfunction "PD7(PTCXY/AIN1)_11") (pintype "bidirectional"))
    )
    (net (code "18") (name "D8") (class "Default")
      (node (ref "J2") (pin "1") (pinfunction "1_1") (pintype "passive"))
      (node (ref "R20") (pin "2") (pinfunction "2_2") (pintype "passive"))
      (node (ref "U1") (pin "12") (pinfunction "PB0(ICP1/CLKO/PTCXY)_12") (pintype "bidirectional"))
    )
    (net (code "19") (name "D9") (class "Default")
      (node (ref "J2") (pin "2") (pinfunction "2_2") (pintype "passive"))
      (node (ref "R19") (pin "2") (pinfunction "2_2") (pintype "passive"))
      (node (ref "U1") (pin "13") (pinfunction "PB1(OC1A/PTCXY)_13") (pintype "bidirectional"))
    )
    (net (code "20") (name "D10") (class "Default")
      (node (ref "J2") (pin "3") (pinfunction "3_3") (pintype "passive"))
      (node (ref "U1") (pin "14") (pinfunction "PB2(~{SS0}/OC1B/PTCXY)_14") (pintype "bidirectional"))
    )
    (net (code "21") (name "D11") (class "Default")
      (node (ref "J2") (pin "4") (pinfunction "4_4") (pintype "passive"))
      (node (ref "J5") (pin "4") (pinfunction "4_4") (pintype "bidirectional"))
      (node (ref "U1") (pin "15") (pinfunction "PB3(MOSI0/TXD1/OC2A/PTCXY)_15") (pintype "bidirectional"))
    )
    (net (code "22") (name "D12") (class "Default")
      (node (ref "J2") (pin "5") (pinfunction "5_5") (pintype "passive"))
      (node (ref "J5") (pin "1") (pinfunction "1_1") (pintype "bidirectional"))
      (node (ref "U1") (pin "16") (pinfunction "PB4(MISO0/RXD1/PTCXY)_16") (pintype "bidirectional"))
    )
    (net (code "23") (name "D13") (class "Default")
      (node (ref "J2") (pin "6") (pinfunction "6_6") (pintype "passive"))
      (node (ref "J5") (pin "3") (pinfunction "3_3") (pintype "bidirectional"))
      (node (ref "R10") (pin "2") (pinfunction "2_2") (pintype "passive"))
      (node (ref "U1") (pin "17") (pinfunction "PB5(PTCXY/XCK0/SCK0)_17") (pintype "bidirectional"))
    )
    (net (code "24") (name "DM") (class "Default")
      (node (ref "C3") (pin "2") (pinfunction "2_2") (pintype "passive"))
      (node (ref "R4") (pin "1") (pinfunction "1_1") (pintype "passive"))
      (node (ref "TP2") (pin "TP") (pinfunction "TP_TP") (pintype "input"))
      (node (ref "U5") (pin "3") (pinfunction "3_3") (pintype "bidirectional"))
      (node (ref "USB1") (pin "A7") (pinfunction "D1-_A7") (pintype "passive"))
      (node (ref "USB1") (pin "B7") (pinfunction "D2-_B7") (pintype "passive"))
      (node (ref "USB2") (pin "D-") (pinfunction "D-_D-") (pintype "bidirectional"))
    )
    (net (code "25") (name "DP") (class "Default")
      (node (ref "C2") (pin "2") (pinfunction "2_2") (pintype "passive"))
      (node (ref "R3") (pin "1") (pinfunction "1_1") (pintype "passive"))
      (node (ref "TP3") (pin "TP") (pinfunction "TP_TP") (pintype "input"))
      (node (ref "U5") (pin "1") (pinfunction "1_1") (pintype "bidirectional"))
      (node (ref "USB1") (pin "A6") (pinfunction "D1+_A6") (pintype "passive"))
      (node (ref "USB1") (pin "B6") (pinfunction "D2+_B6") (pintype "passive"))
      (node (ref "USB2") (pin "D+") (pinfunction "D+_D+") (pintype "bidirectional"))
    )
    (net (code "26") (name "GND") (class "Default")
      (node (ref "ANT1") (pin "1") (pinfunction "GND_1") (pintype "passive"))
      (node (ref "ANT1") (pin "2") (pinfunction "GND_2") (pintype "passive"))
      (node (ref "C1") (pin "1") (pinfunction "1_1") (pintype "passive"))
      (node (ref "C10") (pin "1") (pinfunction "1_1") (pintype "passive"))
      (node (ref "C11") (pin "1") (pinfunction "1_1") (pintype "passive"))
      (node (ref "C12") (pin "1") (pinfunction "1_1") (pintype "passive"))
      (node (ref "C13") (pin "1") (pinfunction "1_1") (pintype "passive"))
      (node (ref "C14") (pin "1") (pinfunction "1_1") (pintype "passive"))
      (node (ref "C15") (pin "1") (pinfunction "1_1") (pintype "passive"))
      (node (ref "C16") (pin "1") (pinfunction "1_1") (pintype "passive"))
      (node (ref "C17") (pin "1") (pinfunction "1_1") (pintype "passive"))
      (node (ref "C18") (pin "1") (pinfunction "1_1") (pintype "passive"))
      (node (ref "C19") (pin "1") (pinfunction "1_1") (pintype "passive"))
      (node (ref "C2") (pin "1") (pinfunction "1_1") (pintype "passive"))
      (node (ref "C20") (pin "1") (pinfunction "1_1") (pintype "passive"))
      (node (ref "C21") (pin "1") (pinfunction "1_1") (pintype "passive"))
      (node (ref "C22") (pin "1") (pinfunction "1_1") (pintype "passive"))
      (node (ref "C23") (pin "1") (pinfunction "1_1") (pintype "passive"))
      (node (ref "C24") (pin "1") (pinfunction "1_1") (pintype "passive"))
      (node (ref "C25") (pin "1") (pinfunction "1_1") (pintype "passive"))
      (node (ref "C26") (pin "1") (pinfunction "1_1") (pintype "passive"))
      (node (ref "C27") (pin "1") (pinfunction "1_1") (pintype "passive"))
      (node (ref "C28") (pin "1") (pinfunction "1_1") (pintype "passive"))
      (node (ref "C29") (pin "1") (pinfunction "1_1") (pintype "passive"))
      (node (ref "C3") (pin "1") (pinfunction "1_1") (pintype "passive"))
      (node (ref "C30") (pin "1") (pinfunction "1_1") (pintype "passive"))
      (node (ref "C31") (pin "1") (pinfunction "1_1") (pintype "passive"))
      (node (ref "C32") (pin "1") (pinfunction "1_1") (pintype "passive"))
      (node (ref "C33") (pin "1") (pinfunction "1_1") (pintype "passive"))
      (node (ref "C34") (pin "1") (pinfunction "1_1") (pintype "passive"))
      (node (ref "C35") (pin "1") (pinfunction "1_1") (pintype "passive"))
      (node (ref "C36") (pin "1") (pinfunction "1_1") (pintype "passive"))
      (node (ref "C37") (pin "1") (pinfunction "1_1") (pintype "passive"))
      (node (ref "C38") (pin "1") (pinfunction "1_1") (pintype "passive"))
      (node (ref "C39") (pin "1") (pinfunction "1_1") (pintype "passive"))
      (node (ref "C4") (pin "1") (pinfunction "1_1") (pintype "passive"))
      (node (ref "C40") (pin "1") (pinfunction "1_1") (pintype "passive"))
      (node (ref "C41") (pin "1") (pinfunction "1_1") (pintype "passive"))
      (node (ref "C42") (pin "1") (pinfunction "1_1") (pintype "passive"))
      (node (ref "C43") (pin "1") (pinfunction "1_1") (pintype "passive"))
      (node (ref "C44") (pin "1") (pinfunction "1_1") (pintype "passive"))
      (node (ref "C45") (pin "1") (pinfunction "1_1") (pintype "passive"))
      (node (ref "C46") (pin "1") (pinfunction "1_1") (pintype "passive"))
      (node (ref "C47") (pin "1") (pinfunction "1_1") (pintype "passive"))
      (node (ref "C48") (pin "1") (pinfunction "1_1") (pintype "passive"))
      (node (ref "C49") (pin "1") (pinfunction "1_1") (pintype "passive"))
      (node (ref "C5") (pin "1") (pinfunction "1_1") (pintype "passive"))
      (node (ref "C50") (pin "1") (pinfunction "1_1") (pintype "passive"))
      (node (ref "C51") (pin "1") (pinfunction "1_1") (pintype "passive"))
      (node (ref "C52") (pin "1") (pinfunction "1_1") (pintype "passive"))
      (node (ref "C53") (pin "1") (pinfunction "1_1") (pintype "passive"))
      (node (ref "C54") (pin "1") (pinfunction "1_1") (pintype "passive"))
      (node (ref "C55") (pin "1") (pinfunction "1_1") (pintype "passive"))
      (node (ref "C56") (pin "1") (pinfunction "1_1") (pintype "passive"))
      (node (ref "C57") (pin "-") (pinfunction "-_-") (pintype "passive"))
      (node (ref "C58") (pin "1") (pinfunction "1_1") (pintype "passive"))
      (node (ref "C59") (pin "1") (pinfunction "1_1") (pintype "passive"))
      (node (ref "C6") (pin "1") (pinfunction "1_1") (pintype "passive"))
      (node (ref "C8") (pin "1") (pinfunction "1_1") (pintype "passive"))
      (node (ref "C9") (pin "1") (pinfunction "1_1") (pintype "passive"))
      (node (ref "D6") (pin "A") (pinfunction "+_A") (pintype "passive"))
      (node (ref "J2") (pin "7") (pinfunction "7_7") (pintype "passive"))
      (node (ref "J4") (pin "2") (pinfunction "2_2") (pintype "passive"))
      (node (ref "J4") (pin "3") (pinfunction "3_3") (pintype "passive"))
      (node (ref "J5") (pin "6") (pinfunction "6_6") (pintype "bidirectional"))
      (node (ref "J6") (pin "4") (pinfunction "4_4") (pintype "bidirectional"))
      (node (ref "J6") (pin "SS1") (pinfunction "SS1_SS1") (pintype "bidirectional"))
      (node (ref "J6") (pin "SS2") (pinfunction "SS2_SS2") (pintype "bidirectional"))
      (node (ref "J7") (pin "1") (pinfunction "1_1") (pintype "passive"))
      (node (ref "K1") (pin "1") (pinfunction "P1_1") (pintype "passive"))
      (node (ref "K1") (pin "2") (pinfunction "P2_2") (pintype "passive"))
      (node (ref "K2") (pin "SS1") (pinfunction "SS1_SS1") (pintype "bidirectional"))
      (node (ref "K2") (pin "SS2") (pinfunction "SS2_SS2") (pintype "bidirectional"))
      (node (ref "K2") (pin "SS3") (pinfunction "SS3_SS3") (pintype "bidirectional"))
      (node (ref "K2") (pin "SS4") (pinfunction "SS4_SS4") (pintype "bidirectional"))
      (node (ref "L1") (pin "1") (pinfunction "1_1") (pintype "passive"))
      (node (ref "Q1") (pin "2") (pinfunction "S_2") (pintype "bidirectional"))
      (node (ref "Q5") (pin "2") (pinfunction "E_2") (pintype "bidirectional"))
      (node (ref "R1") (pin "1") (pinfunction "1_1") (pintype "passive"))
      (node (ref "R11") (pin "1") (pinfunction "1_1") (pintype "passive"))
      (node (ref "R13") (pin "1") (pinfunction "1_1") (pintype "passive"))
      (node (ref "R2") (pin "1") (pinfunction "1_1") (pintype "passive"))
      (node (ref "R6") (pin "2") (pinfunction "2_2") (pintype "passive"))
      (node (ref "R8") (pin "1") (pinfunction "1_1") (pintype "passive"))
      (node (ref "TP4") (pin "TP") (pinfunction "TP_TP") (pintype "input"))
      (node (ref "U1") (pin "21") (pinfunction "GND_21") (pintype "power_in"))
      (node (ref "U1") (pin "5") (pinfunction "GND_5") (pintype "power_in"))
      (node (ref "U2") (pin "2") (pinfunction "GND_2") (pintype "power_in"))
      (node (ref "U2") (pin "25") (pinfunction "GND_25") (pintype "power_in"))
      (node (ref "U3") (pin "1") (pinfunction "ADJ_1") (pintype "input"))
      (node (ref "U4") (pin "1") (pinfunction "ADJ_1") (pintype "input"))
      (node (ref "U5") (pin "2") (pinfunction "2_2") (pintype "bidirectional"))
      (node (ref "U6") (pin "4") (pinfunction "GND_4") (pintype "bidirectional"))
      (node (ref "U7") (pin "1") (pinfunction "GND_1") (pintype "bidirectional"))
      (node (ref "U7") (pin "2") (pinfunction "GND_2") (pintype "bidirectional"))
      (node (ref "U7") (pin "20") (pinfunction "GND_20") (pintype "bidirectional"))
      (node (ref "U7") (pin "22") (pinfunction "GND_22") (pintype "bidirectional"))
      (node (ref "U7") (pin "27") (pinfunction "GND_27") (pintype "bidirectional"))
      (node (ref "U7") (pin "28") (pinfunction "GND_28") (pintype "bidirectional"))
      (node (ref "U7") (pin "29") (pinfunction "GND_29") (pintype "bidirectional"))
      (node (ref "U7") (pin "3") (pinfunction "GND_3") (pintype "bidirectional"))
      (node (ref "U7") (pin "31") (pinfunction "GND_31") (pintype "bidirectional"))
      (node (ref "U7") (pin "4") (pinfunction "GND_4") (pintype "bidirectional"))
      (node (ref "USB1") (pin "A1") (pinfunction "GND1_A1") (pintype "passive"))
      (node (ref "USB1") (pin "A12") (pinfunction "GND2_A12") (pintype "passive"))
      (node (ref "USB1") (pin "B1") (pinfunction "GND3_B1") (pintype "passive"))
      (node (ref "USB1") (pin "B12") (pinfunction "GND4_B12") (pintype "passive"))
      (node (ref "USB1") (pin "S1") (pinfunction "SHIELD_S1") (pintype "passive"))
      (node (ref "USB1") (pin "S2") (pinfunction "SHIELD_S2") (pintype "passive"))
      (node (ref "USB1") (pin "S3") (pinfunction "SHIELD_S3") (pintype "passive"))
      (node (ref "USB1") (pin "S4") (pinfunction "SHIELD_S4") (pintype "passive"))
      (node (ref "USB2") (pin "GND") (pinfunction "GND_GND") (pintype "bidirectional"))
      (node (ref "X1") (pin "2") (pinfunction "3_2") (pintype "passive"))
      (node (ref "X1") (pin "4") (pinfunction "3_4") (pintype "passive"))
    )
    (net (code "27") (name "Net-(ANT1-SIGNAL)") (class "Default")
      (node (ref "ANT1") (pin "3") (pinfunction "SIGNAL_3") (pintype "passive"))
      (node (ref "R22") (pin "1") (pinfunction "1_1") (pintype "passive"))
    )
    (net (code "28") (name "Net-(C60-Pad1)") (class "Default")
      (node (ref "C60") (pin "1") (pinfunction "1_1") (pintype "passive"))
      (node (ref "L1") (pin "2") (pinfunction "2_2") (pintype "passive"))
      (node (ref "R22") (pin "2") (pinfunction "2_2") (pintype "passive"))
    )
    (net (code "29") (name "Net-(D3-K)") (class "Default")
      (node (ref "C29") (pin "2") (pinfunction "2_2") (pintype "passive"))
      (node (ref "C34") (pin "2") (pinfunction "2_2") (pintype "passive"))
      (node (ref "D3") (pin "1") (pinfunction "K_1") (pintype "bidirectional"))
      (node (ref "D5") (pin "C") (pinfunction "-_C") (pintype "passive"))
      (node (ref "Q4") (pin "2") (pinfunction "S_2") (pintype "passive"))
      (node (ref "U4") (pin "3") (pinfunction "IN_3") (pintype "input"))
    )
    (net (code "30") (name "Net-(D5-+)") (class "Default")
      (node (ref "D5") (pin "A") (pinfunction "+_A") (pintype "passive"))
      (node (ref "Q4") (pin "1") (pinfunction "G_1") (pintype "passive"))
      (node (ref "R13") (pin "2") (pinfunction "2_2") (pintype "passive"))
    )
    (net (code "31") (name "Net-(LED1-Pad-)") (class "Default")
      (node (ref "LED1") (pin "-") (pinfunction "-_-") (pintype "passive"))
      (node (ref "R8") (pin "2") (pinfunction "2_2") (pintype "passive"))
    )
    (net (code "32") (name "Net-(LED2-Pad-)") (class "Default")
      (node (ref "LED2") (pin "-") (pinfunction "-_-") (pintype "passive"))
      (node (ref "R9") (pin "2") (pinfunction "2_2") (pintype "passive"))
    )
    (net (code "33") (name "Net-(Q1-D)") (class "Default")
      (node (ref "Q1") (pin "3") (pinfunction "D_3") (pintype "bidirectional"))
      (node (ref "R9") (pin "1") (pinfunction "1_1") (pintype "passive"))
    )
    (net (code "34") (name "Net-(Q1-G)") (class "Default")
      (node (ref "Q1") (pin "1") (pinfunction "G_1") (pintype "bidirectional"))
      (node (ref "R10") (pin "1") (pinfunction "1_1") (pintype "passive"))
      (node (ref "R11") (pin "2") (pinfunction "2_2") (pintype "passive"))
    )
    (net (code "35") (name "Net-(U1-PB6(XTAL1{slash}TOSC1))") (class "Default")
      (node (ref "C20") (pin "2") (pinfunction "2_2") (pintype "passive"))
      (node (ref "U1") (pin "7") (pinfunction "PB6(XTAL1/TOSC1)_7") (pintype "bidirectional"))
      (node (ref "X1") (pin "1") (pinfunction "1_1") (pintype "passive"))
    )
    (net (code "36") (name "Net-(U1-PB7(XTAL2{slash}TOSC2))") (class "Default")
      (node (ref "C19") (pin "2") (pinfunction "2_2") (pintype "passive"))
      (node (ref "U1") (pin "8") (pinfunction "PB7(XTAL2/TOSC2)_8") (pintype "bidirectional"))
      (node (ref "X1") (pin "3") (pinfunction "2_3") (pintype "passive"))
    )
    (net (code "37") (name "Net-(U2-D+)") (class "Default")
      (node (ref "R3") (pin "2") (pinfunction "2_2") (pintype "passive"))
      (node (ref "U2") (pin "3") (pinfunction "D+_3") (pintype "bidirectional"))
    )
    (net (code "38") (name "Net-(U2-D-)") (class "Default")
      (node (ref "R4") (pin "2") (pinfunction "2_2") (pintype "passive"))
      (node (ref "U2") (pin "4") (pinfunction "D-_4") (pintype "bidirectional"))
    )
    (net (code "39") (name "Net-(U2-DTR)") (class "Default")
      (node (ref "C7") (pin "2") (pinfunction "2_2") (pintype "passive"))
      (node (ref "U2") (pin "23") (pinfunction "DTR_23") (pintype "output"))
    )
    (net (code "40") (name "Net-(U2-VBUS)") (class "Default")
      (node (ref "R5") (pin "1") (pinfunction "1_1") (pintype "passive"))
      (node (ref "R6") (pin "1") (pinfunction "1_1") (pintype "passive"))
      (node (ref "U2") (pin "8") (pinfunction "VBUS_8") (pintype "input"))
    )
    (net (code "41") (name "Net-(U2-VPP)") (class "Default")
      (node (ref "C8") (pin "2") (pinfunction "2_2") (pintype "passive"))
      (node (ref "U2") (pin "16") (pinfunction "VPP_16") (pintype "passive"))
    )
    (net (code "42") (name "Net-(U2-~{RST})") (class "Default")
      (node (ref "R7") (pin "2") (pinfunction "2_2") (pintype "passive"))
      (node (ref "U2") (pin "9") (pinfunction "~{RST}_9") (pintype "input"))
    )
    (net (code "43") (name "Net-(U3-IN)") (class "Default")
      (node (ref "C23") (pin "2") (pinfunction "2_2") (pintype "passive"))
      (node (ref "C26") (pin "2") (pinfunction "2_2") (pintype "passive"))
      (node (ref "F1") (pin "2") (pinfunction "2_2") (pintype "bidirectional"))
      (node (ref "U3") (pin "3") (pinfunction "IN_3") (pintype "input"))
    )
    (net (code "44") (name "Net-(U6-EN)") (class "Default")
      (node (ref "R18") (pin "2") (pinfunction "2_2") (pintype "passive"))
      (node (ref "U6") (pin "5") (pinfunction "EN_5") (pintype "bidirectional"))
    )
    (net (code "45") (name "Net-(U7-CPULED)") (class "Default")
      (node (ref "TP13") (pin "TP") (pinfunction "TP_TP") (pintype "input"))
      (node (ref "U7") (pin "11") (pinfunction "CPULED_11") (pintype "bidirectional"))
    )
    (net (code "46") (name "Net-(U7-DBG_EN)") (class "Default")
      (node (ref "TP18") (pin "TP") (pinfunction "TP_TP") (pintype "input"))
      (node (ref "U7") (pin "18") (pinfunction "DBG_EN_18") (pintype "bidirectional"))
    )
    (net (code "47") (name "Net-(U7-GPIO0)") (class "Default")
      (node (ref "TP19") (pin "TP") (pinfunction "TP_TP") (pintype "input"))
      (node (ref "U7") (pin "23") (pinfunction "GPIO0_23") (pintype "bidirectional"))
    )
    (net (code "48") (name "Net-(U7-GPIO1)") (class "Default")
      (node (ref "TP20") (pin "TP") (pinfunction "TP_TP") (pintype "input"))
      (node (ref "U7") (pin "24") (pinfunction "GPIO1_24") (pintype "bidirectional"))
    )
    (net (code "49") (name "Net-(U7-GPIO2)") (class "Default")
      (node (ref "TP21") (pin "TP") (pinfunction "TP_TP") (pintype "input"))
      (node (ref "U7") (pin "25") (pinfunction "GPIO2_25") (pintype "bidirectional"))
    )
    (net (code "50") (name "Net-(U7-GPIO3)") (class "Default")
      (node (ref "TP22") (pin "TP") (pinfunction "TP_TP") (pintype "input"))
      (node (ref "U7") (pin "26") (pinfunction "GPIO3_26") (pintype "bidirectional"))
    )
    (net (code "51") (name "Net-(U7-GPIO4)") (class "Default")
      (node (ref "TP12") (pin "TP") (pinfunction "TP_TP") (pintype "input"))
      (node (ref "U7") (pin "10") (pinfunction "GPIO4_10") (pintype "bidirectional"))
    )
    (net (code "52") (name "Net-(U7-GPIO5)") (class "Default")
      (node (ref "TP11") (pin "TP") (pinfunction "TP_TP") (pintype "input"))
      (node (ref "U7") (pin "9") (pinfunction "GPIO5_9") (pintype "bidirectional"))
    )
    (net (code "53") (name "Net-(U7-GPIO6)") (class "Default")
      (node (ref "TP10") (pin "TP") (pinfunction "TP_TP") (pintype "input"))
      (node (ref "U7") (pin "8") (pinfunction "GPIO6_8") (pintype "bidirectional"))
    )
    (net (code "54") (name "Net-(U7-GPIO7)") (class "Default")
      (node (ref "TP9") (pin "TP") (pinfunction "TP_TP") (pintype "input"))
      (node (ref "U7") (pin "7") (pinfunction "GPIO7_7") (pintype "bidirectional"))
    )
    (net (code "55") (name "Net-(U7-GPIO8)") (class "Default")
      (node (ref "TP8") (pin "TP") (pinfunction "TP_TP") (pintype "input"))
      (node (ref "U7") (pin "6") (pinfunction "GPIO8_6") (pintype "bidirectional"))
    )
    (net (code "56") (name "Net-(U7-GPIO9)") (class "Default")
      (node (ref "TP15") (pin "TP") (pinfunction "TP_TP") (pintype "input"))
      (node (ref "U7") (pin "13") (pinfunction "GPIO9_13") (pintype "bidirectional"))
    )
    (net (code "57") (name "Net-(U7-NC3{slash}SYSCLK)") (class "Default")
      (node (ref "TP7") (pin "TP") (pinfunction "TP_TP") (pintype "input"))
      (node (ref "U7") (pin "5") (pinfunction "NC3/SYSCLK_5") (pintype "bidirectional"))
    )
    (net (code "58") (name "Net-(U7-RADIOLED)") (class "Default")
      (node (ref "TP14") (pin "TP") (pinfunction "TP_TP") (pintype "input"))
      (node (ref "U7") (pin "12") (pinfunction "RADIOLED_12") (pintype "bidirectional"))
    )
    (net (code "59") (name "Net-(U7-RF_IO)") (class "Default")
      (node (ref "C60") (pin "2") (pinfunction "2_2") (pintype "passive"))
      (node (ref "U7") (pin "30") (pinfunction "RF_IO_30") (pintype "bidirectional"))
    )
    (net (code "60") (name "Net-(U7-RXLED{slash}DBG_DATA)") (class "Default")
      (node (ref "TP16") (pin "TP") (pinfunction "TP_TP") (pintype "input"))
      (node (ref "U7") (pin "16") (pinfunction "RXLED/DBG_DATA_16") (pintype "bidirectional"))
    )
    (net (code "61") (name "Net-(U7-TXLED_DBG_CLK)") (class "Default")
      (node (ref "TP17") (pin "TP") (pinfunction "TP_TP") (pintype "input"))
      (node (ref "U7") (pin "17") (pinfunction "TXLED_DBG_CLK_17") (pintype "bidirectional"))
    )
    (net (code "62") (name "Net-(U7-UARTRX)") (class "Default")
      (node (ref "R19") (pin "1") (pinfunction "1_1") (pintype "passive"))
      (node (ref "U7") (pin "15") (pinfunction "UARTRX_15") (pintype "bidirectional"))
    )
    (net (code "63") (name "Net-(U7-UARTTX)") (class "Default")
      (node (ref "R20") (pin "1") (pinfunction "1_1") (pintype "passive"))
      (node (ref "U7") (pin "14") (pinfunction "UARTTX_14") (pintype "bidirectional"))
    )
    (net (code "64") (name "Net-(USB1-CC1)") (class "Default")
      (node (ref "R1") (pin "2") (pinfunction "2_2") (pintype "passive"))
      (node (ref "TP5") (pin "TP") (pinfunction "TP_TP") (pintype "input"))
      (node (ref "USB1") (pin "A5") (pinfunction "CC1_A5") (pintype "passive"))
    )
    (net (code "65") (name "Net-(USB1-CC2)") (class "Default")
      (node (ref "R2") (pin "2") (pinfunction "2_2") (pintype "passive"))
      (node (ref "TP6") (pin "TP") (pinfunction "TP_TP") (pintype "input"))
      (node (ref "USB1") (pin "B5") (pinfunction "CC2_B5") (pintype "passive"))
    )
    (net (code "66") (name "PE0") (class "Default")
      (node (ref "J4") (pin "12") (pinfunction "12_12") (pintype "passive"))
      (node (ref "U1") (pin "3") (pinfunction "PE0(SDA1/ICP4/ACO/PTCXY)_3") (pintype "bidirectional"))
    )
    (net (code "67") (name "PE1") (class "Default")
      (node (ref "J4") (pin "11") (pinfunction "11_11") (pintype "passive"))
      (node (ref "U1") (pin "6") (pinfunction "PE1(SCL1/T4/PTCXY)_6") (pintype "bidirectional"))
    )
    (net (code "68") (name "PE2") (class "Default")
      (node (ref "J4") (pin "10") (pinfunction "10_10") (pintype "passive"))
      (node (ref "U1") (pin "19") (pinfunction "PE2(ADC6/PTCY/ICP3/~{SS1})_19") (pintype "bidirectional"))
    )
    (net (code "69") (name "PE3") (class "Default")
      (node (ref "J4") (pin "9") (pinfunction "9_9") (pintype "passive"))
      (node (ref "U1") (pin "22") (pinfunction "PE3(ADC7/PTCY/T3/MOSI1)_22") (pintype "bidirectional"))
    )
    (net (code "70") (name "RESET") (class "Default")
      (node (ref "C10") (pin "2") (pinfunction "2_2") (pintype "passive"))
      (node (ref "C7") (pin "1") (pinfunction "1_1") (pintype "passive"))
      (node (ref "D4") (pin "A") (pinfunction "A_A") (pintype "passive"))
      (node (ref "J4") (pin "6") (pinfunction "6_6") (pintype "passive"))
      (node (ref "J5") (pin "5") (pinfunction "5_5") (pintype "bidirectional"))
      (node (ref "K1") (pin "3") (pinfunction "S1_3") (pintype "passive"))
      (node (ref "K1") (pin "4") (pinfunction "S2_4") (pintype "passive"))
      (node (ref "R12") (pin "1") (pinfunction "1_1") (pintype "passive"))
      (node (ref "U1") (pin "29") (pinfunction "PC6(~{RESET})_29") (pintype "bidirectional"))
    )
    (net (code "71") (name "RST_N") (class "Default")
      (node (ref "C54") (pin "2") (pinfunction "2_2") (pintype "passive"))
      (node (ref "Q5") (pin "3") (pinfunction "C_3") (pintype "bidirectional"))
      (node (ref "R21") (pin "1") (pinfunction "1_1") (pintype "passive"))
      (node (ref "U7") (pin "19") (pinfunction "RST_N_19") (pintype "bidirectional"))
    )
    (net (code "72") (name "SCL") (class "Default")
      (node (ref "J2") (pin "10") (pinfunction "10_10") (pintype "passive"))
      (node (ref "J6") (pin "1") (pinfunction "1_1") (pintype "bidirectional"))
      (node (ref "J7") (pin "4") (pinfunction "4_4") (pintype "passive"))
      (node (ref "R14") (pin "1") (pinfunction "1_1") (pintype "passive"))
      (node (ref "U6") (pin "2") (pinfunction "SCLA_2") (pintype "bidirectional"))
    )
    (net (code "73") (name "SDA") (class "Default")
      (node (ref "J2") (pin "9") (pinfunction "9_9") (pintype "passive"))
      (node (ref "J6") (pin "2") (pinfunction "2_2") (pintype "bidirectional"))
      (node (ref "J7") (pin "3") (pinfunction "3_3") (pintype "passive"))
      (node (ref "R15") (pin "1") (pinfunction "1_1") (pintype "passive"))
      (node (ref "U6") (pin "3") (pinfunction "SDAA_3") (pintype "bidirectional"))
    )
    (net (code "74") (name "VCC") (class "Default")
      (node (ref "C11") (pin "2") (pinfunction "2_2") (pintype "passive"))
      (node (ref "C12") (pin "2") (pinfunction "2_2") (pintype "passive"))
      (node (ref "C13") (pin "2") (pinfunction "2_2") (pintype "passive"))
      (node (ref "C14") (pin "2") (pinfunction "2_2") (pintype "passive"))
      (node (ref "C15") (pin "2") (pinfunction "2_2") (pintype "passive"))
      (node (ref "C16") (pin "2") (pinfunction "2_2") (pintype "passive"))
      (node (ref "C17") (pin "2") (pinfunction "2_2") (pintype "passive"))
      (node (ref "C18") (pin "2") (pinfunction "2_2") (pintype "passive"))
      (node (ref "C21") (pin "2") (pinfunction "2_2") (pintype "passive"))
      (node (ref "C22") (pin "2") (pinfunction "2_2") (pintype "passive"))
      (node (ref "C39") (pin "2") (pinfunction "2_2") (pintype "passive"))
      (node (ref "C4") (pin "2") (pinfunction "2_2") (pintype "passive"))
      (node (ref "C40") (pin "2") (pinfunction "2_2") (pintype "passive"))
      (node (ref "C41") (pin "2") (pinfunction "2_2") (pintype "passive"))
      (node (ref "C42") (pin "2") (pinfunction "2_2") (pintype "passive"))
      (node (ref "C43") (pin "2") (pinfunction "2_2") (pintype "passive"))
      (node (ref "C44") (pin "2") (pinfunction "2_2") (pintype "passive"))
      (node (ref "C5") (pin "2") (pinfunction "2_2") (pintype "passive"))
      (node (ref "C53") (pin "2") (pinfunction "2_2") (pintype "passive"))
      (node (ref "C6") (pin "2") (pinfunction "2_2") (pintype "passive"))
      (node (ref "D4") (pin "C") (pinfunction "C_C") (pintype "passive"))
      (node (ref "J4") (pin "7") (pinfunction "7_7") (pintype "passive"))
      (node (ref "K2") (pin "COM") (pinfunction "COM_COM") (pintype "bidirectional"))
      (node (ref "LED1") (pin "+") (pinfunction "+_+") (pintype "passive"))
      (node (ref "LED2") (pin "+") (pinfunction "+_+") (pintype "passive"))
      (node (ref "R12") (pin "2") (pinfunction "2_2") (pintype "passive"))
      (node (ref "R16") (pin "2") (pinfunction "2_2") (pintype "passive"))
      (node (ref "R17") (pin "2") (pinfunction "2_2") (pintype "passive"))
      (node (ref "R18") (pin "1") (pinfunction "1_1") (pintype "passive"))
      (node (ref "R7") (pin "1") (pinfunction "1_1") (pintype "passive"))
      (node (ref "U1") (pin "18") (pinfunction "AVCC_18") (pintype "power_in"))
      (node (ref "U1") (pin "4") (pinfunction "VCC_4") (pintype "power_in"))
      (node (ref "U2") (pin "5") (pinfunction "VIO_5") (pintype "power_in"))
      (node (ref "U2") (pin "6") (pinfunction "VDD_6") (pintype "power_in"))
      (node (ref "U2") (pin "7") (pinfunction "REGIN_7") (pintype "input"))
      (node (ref "U6") (pin "8") (pinfunction "VCC(B)_8") (pintype "bidirectional"))
    )
    (net (code "75") (name "VCCIO") (class "Default")
      (node (ref "C27") (pin "2") (pinfunction "2_2") (pintype "passive"))
      (node (ref "C28") (pin "2") (pinfunction "2_2") (pintype "passive"))
      (node (ref "C33") (pin "2") (pinfunction "2_2") (pintype "passive"))
      (node (ref "D1") (pin "2") (pinfunction "A_2") (pintype "bidirectional"))
      (node (ref "D2") (pin "2") (pinfunction "A_2") (pintype "bidirectional"))
      (node (ref "Q2") (pin "1") (pinfunction "G_1") (pintype "passive"))
      (node (ref "Q3") (pin "1") (pinfunction "G_1") (pintype "passive"))
      (node (ref "U4") (pin "2") (pinfunction "OUT_2") (pintype "output"))
      (node (ref "U4") (pin "4") (pinfunction "OUT_4") (pintype "output"))
    )
    (net (code "76") (name "VIN") (class "Default")
      (node (ref "C35") (pin "2") (pinfunction "2_2") (pintype "passive"))
      (node (ref "C36") (pin "2") (pinfunction "2_2") (pintype "passive"))
      (node (ref "C48") (pin "2") (pinfunction "2_2") (pintype "passive"))
      (node (ref "D2") (pin "1") (pinfunction "K_1") (pintype "bidirectional"))
      (node (ref "D3") (pin "2") (pinfunction "A_2") (pintype "bidirectional"))
      (node (ref "J4") (pin "1") (pinfunction "1_1") (pintype "passive"))
      (node (ref "Q3") (pin "2") (pinfunction "S_2") (pintype "passive"))
      (node (ref "Q4") (pin "3") (pinfunction "D_3") (pintype "passive"))
    )
    (net (code "77") (name "V_USB") (class "Default")
      (node (ref "C1") (pin "2") (pinfunction "2_2") (pintype "passive"))
      (node (ref "Q2") (pin "3") (pinfunction "D_3") (pintype "passive"))
      (node (ref "Q3") (pin "3") (pinfunction "D_3") (pintype "passive"))
      (node (ref "R5") (pin "2") (pinfunction "2_2") (pintype "passive"))
      (node (ref "TP1") (pin "TP") (pinfunction "TP_TP") (pintype "input"))
      (node (ref "U5") (pin "5") (pinfunction "5_5") (pintype "bidirectional"))
      (node (ref "USB1") (pin "A4") (pinfunction "VBUS1_A4") (pintype "passive"))
      (node (ref "USB1") (pin "A9") (pinfunction "VBUS2_A9") (pintype "passive"))
      (node (ref "USB1") (pin "B4") (pinfunction "VBUS3_B4") (pintype "passive"))
      (node (ref "USB1") (pin "B9") (pinfunction "VBUS4_B9") (pintype "passive"))
      (node (ref "USB2") (pin "VBUS") (pinfunction "VBUS_VBUS") (pintype "bidirectional"))
    )
    (net (code "78") (name "unconnected-(K1-G-Pad5)") (class "Default")
      (node (ref "K1") (pin "5") (pinfunction "G_5") (pintype "passive"))
    )
    (net (code "79") (name "unconnected-(U2-CTS-Pad18)") (class "Default")
      (node (ref "U2") (pin "18") (pinfunction "CTS_18") (pintype "input"))
    )
    (net (code "80") (name "unconnected-(U2-DCD-Pad24)") (class "Default")
      (node (ref "U2") (pin "24") (pinfunction "DCD_24") (pintype "input"))
    )
    (net (code "81") (name "unconnected-(U2-DSR-Pad22)") (class "Default")
      (node (ref "U2") (pin "22") (pinfunction "DSR_22") (pintype "input"))
    )
    (net (code "82") (name "unconnected-(U2-GPIO.0-Pad14)") (class "Default")
      (node (ref "U2") (pin "14") (pinfunction "GPIO.0_14") (pintype "bidirectional"))
    )
    (net (code "83") (name "unconnected-(U2-GPIO.1-Pad13)") (class "Default")
      (node (ref "U2") (pin "13") (pinfunction "GPIO.1_13") (pintype "bidirectional"))
    )
    (net (code "84") (name "unconnected-(U2-GPIO.2-Pad12)") (class "Default")
      (node (ref "U2") (pin "12") (pinfunction "GPIO.2_12") (pintype "bidirectional"))
    )
    (net (code "85") (name "unconnected-(U2-GPIO.3-Pad11)") (class "Default")
      (node (ref "U2") (pin "11") (pinfunction "GPIO.3_11") (pintype "bidirectional"))
    )
    (net (code "86") (name "unconnected-(U2-NC-Pad10)") (class "Default")
      (node (ref "U2") (pin "10") (pinfunction "NC_10") (pintype "bidirectional"))
    )
    (net (code "87") (name "unconnected-(U2-RI-Pad1)") (class "Default")
      (node (ref "U2") (pin "1") (pinfunction "RI_1") (pintype "input"))
    )
    (net (code "88") (name "unconnected-(U2-RTS-Pad19)") (class "Default")
      (node (ref "U2") (pin "19") (pinfunction "RTS_19") (pintype "output"))
    )
    (net (code "89") (name "unconnected-(U2-SUSPEND-Pad17)") (class "Default")
      (node (ref "U2") (pin "17") (pinfunction "SUSPEND_17") (pintype "output"))
    )
    (net (code "90") (name "unconnected-(U2-~{SUSPEND}-Pad15)") (class "Default")
      (node (ref "U2") (pin "15") (pinfunction "~{SUSPEND}_15") (pintype "output"))
    )
    (net (code "91") (name "unconnected-(USB1-RX1+-PadB11)") (class "Default")
      (node (ref "USB1") (pin "B11") (pinfunction "RX1+_B11") (pintype "passive"))
    )
    (net (code "92") (name "unconnected-(USB1-RX1--PadB10)") (class "Default")
      (node (ref "USB1") (pin "B10") (pinfunction "RX1-_B10") (pintype "passive"))
    )
    (net (code "93") (name "unconnected-(USB1-RX2+-PadA11)") (class "Default")
      (node (ref "USB1") (pin "A11") (pinfunction "RX2+_A11") (pintype "passive"))
    )
    (net (code "94") (name "unconnected-(USB1-RX2--PadA10)") (class "Default")
      (node (ref "USB1") (pin "A10") (pinfunction "RX2-_A10") (pintype "passive"))
    )
    (net (code "95") (name "unconnected-(USB1-SBU1-PadA8)") (class "Default")
      (node (ref "USB1") (pin "A8") (pinfunction "SBU1_A8") (pintype "passive"))
    )
    (net (code "96") (name "unconnected-(USB1-SBU2-PadB8)") (class "Default")
      (node (ref "USB1") (pin "B8") (pinfunction "SBU2_B8") (pintype "passive"))
    )
    (net (code "97") (name "unconnected-(USB1-TX1+-PadA2)") (class "Default")
      (node (ref "USB1") (pin "A2") (pinfunction "TX1+_A2") (pintype "passive"))
    )
    (net (code "98") (name "unconnected-(USB1-TX1--PadA3)") (class "Default")
      (node (ref "USB1") (pin "A3") (pinfunction "TX1-_A3") (pintype "passive"))
    )
    (net (code "99") (name "unconnected-(USB1-TX2+-PadB2)") (class "Default")
      (node (ref "USB1") (pin "B2") (pinfunction "TX2+_B2") (pintype "passive"))
    )
    (net (code "100") (name "unconnected-(USB1-TX2--PadB3)") (class "Default")
      (node (ref "USB1") (pin "B3") (pinfunction "TX2-_B3") (pintype "passive"))
    )
  )
)
